# CurrentController.net
KiCad netlist of a schematic drawn in EAGLE
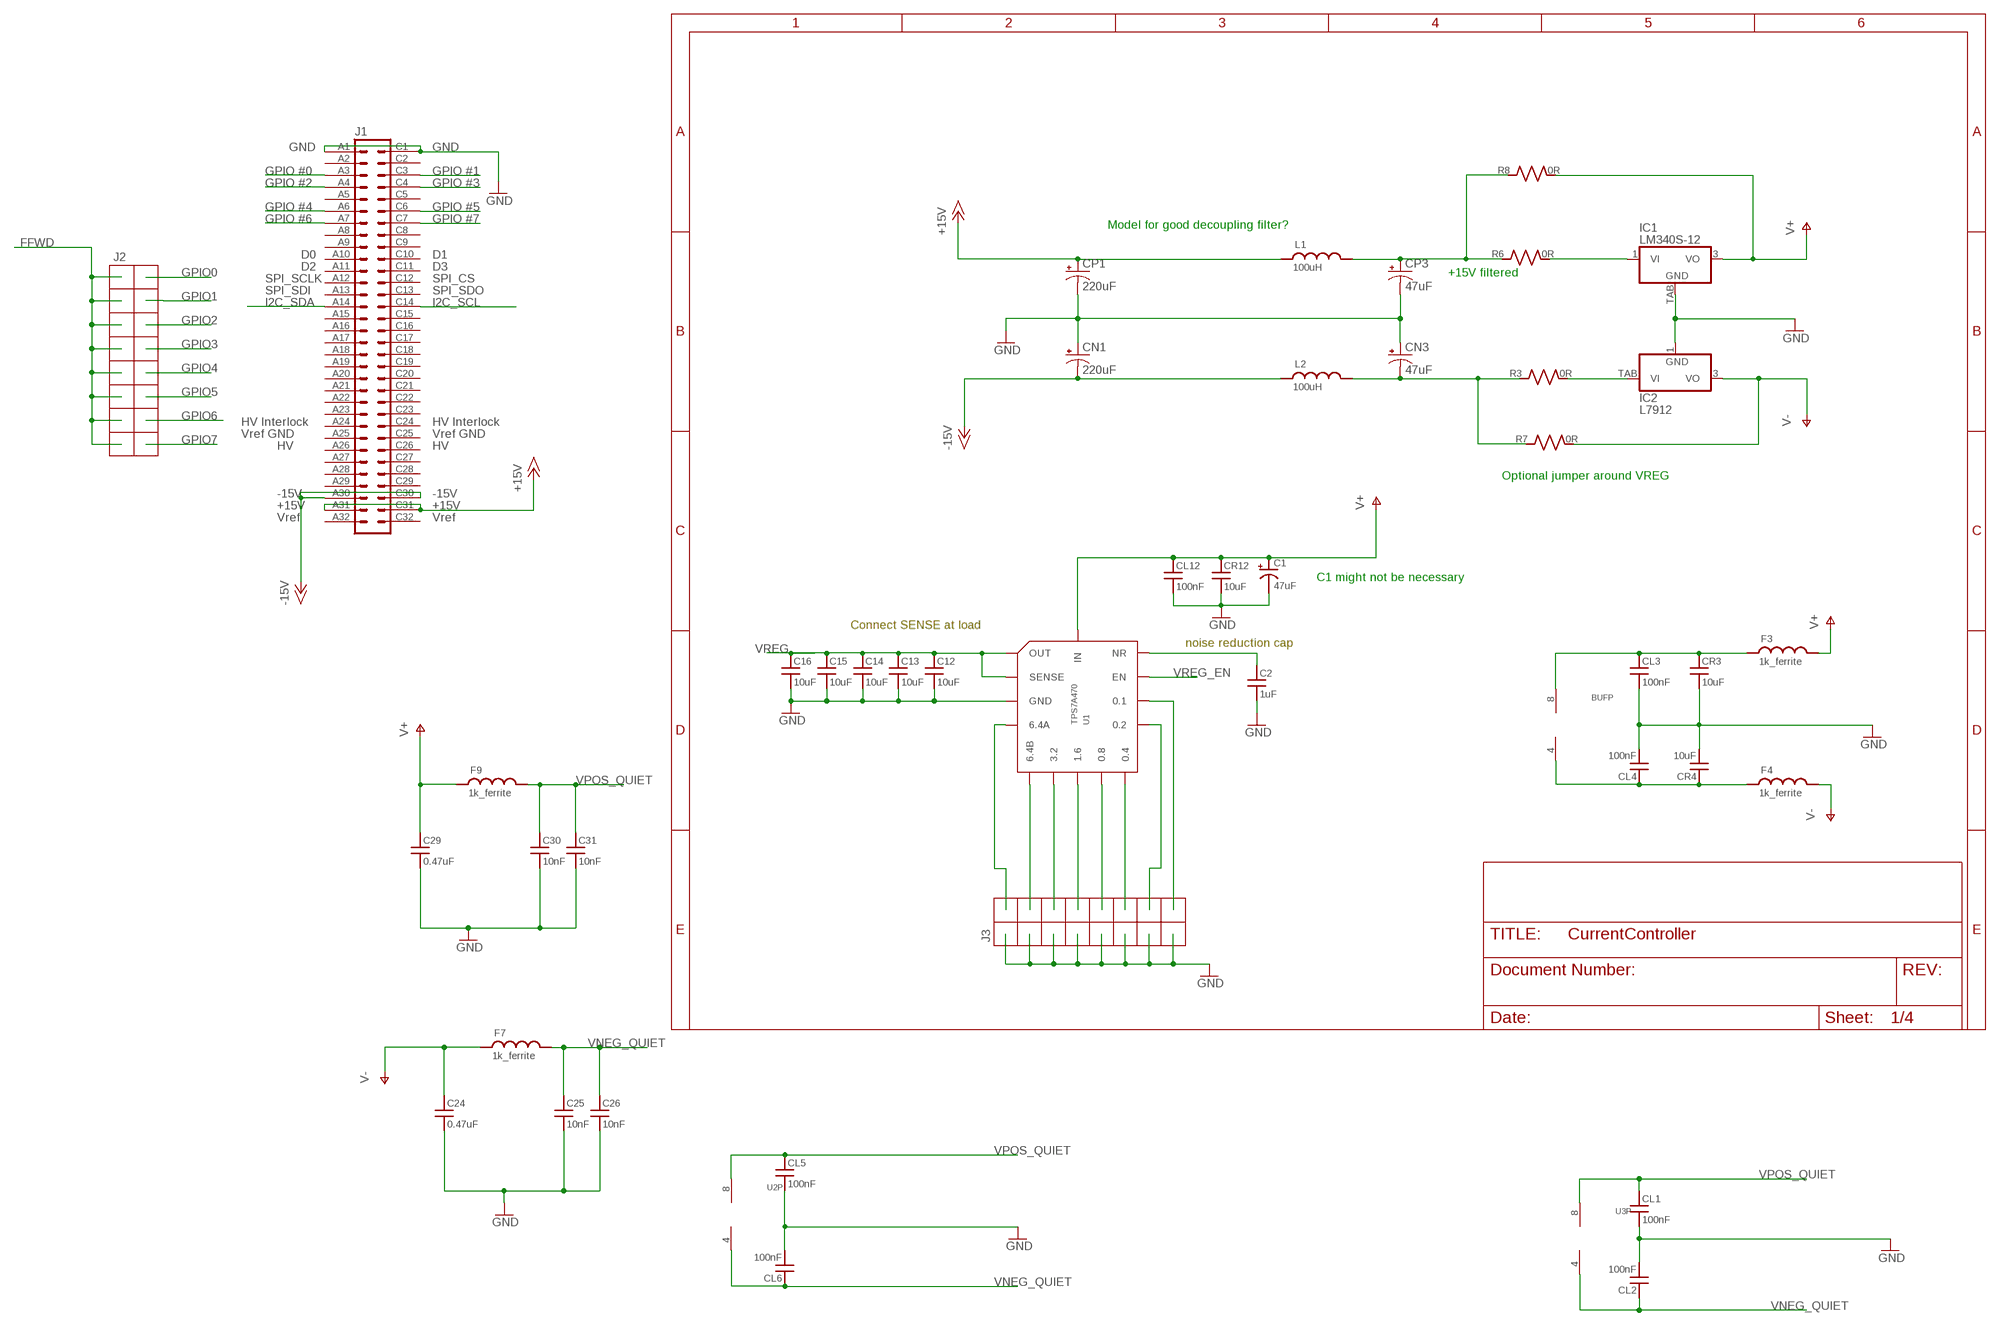
[diagram p0: schematic, sheet 1]
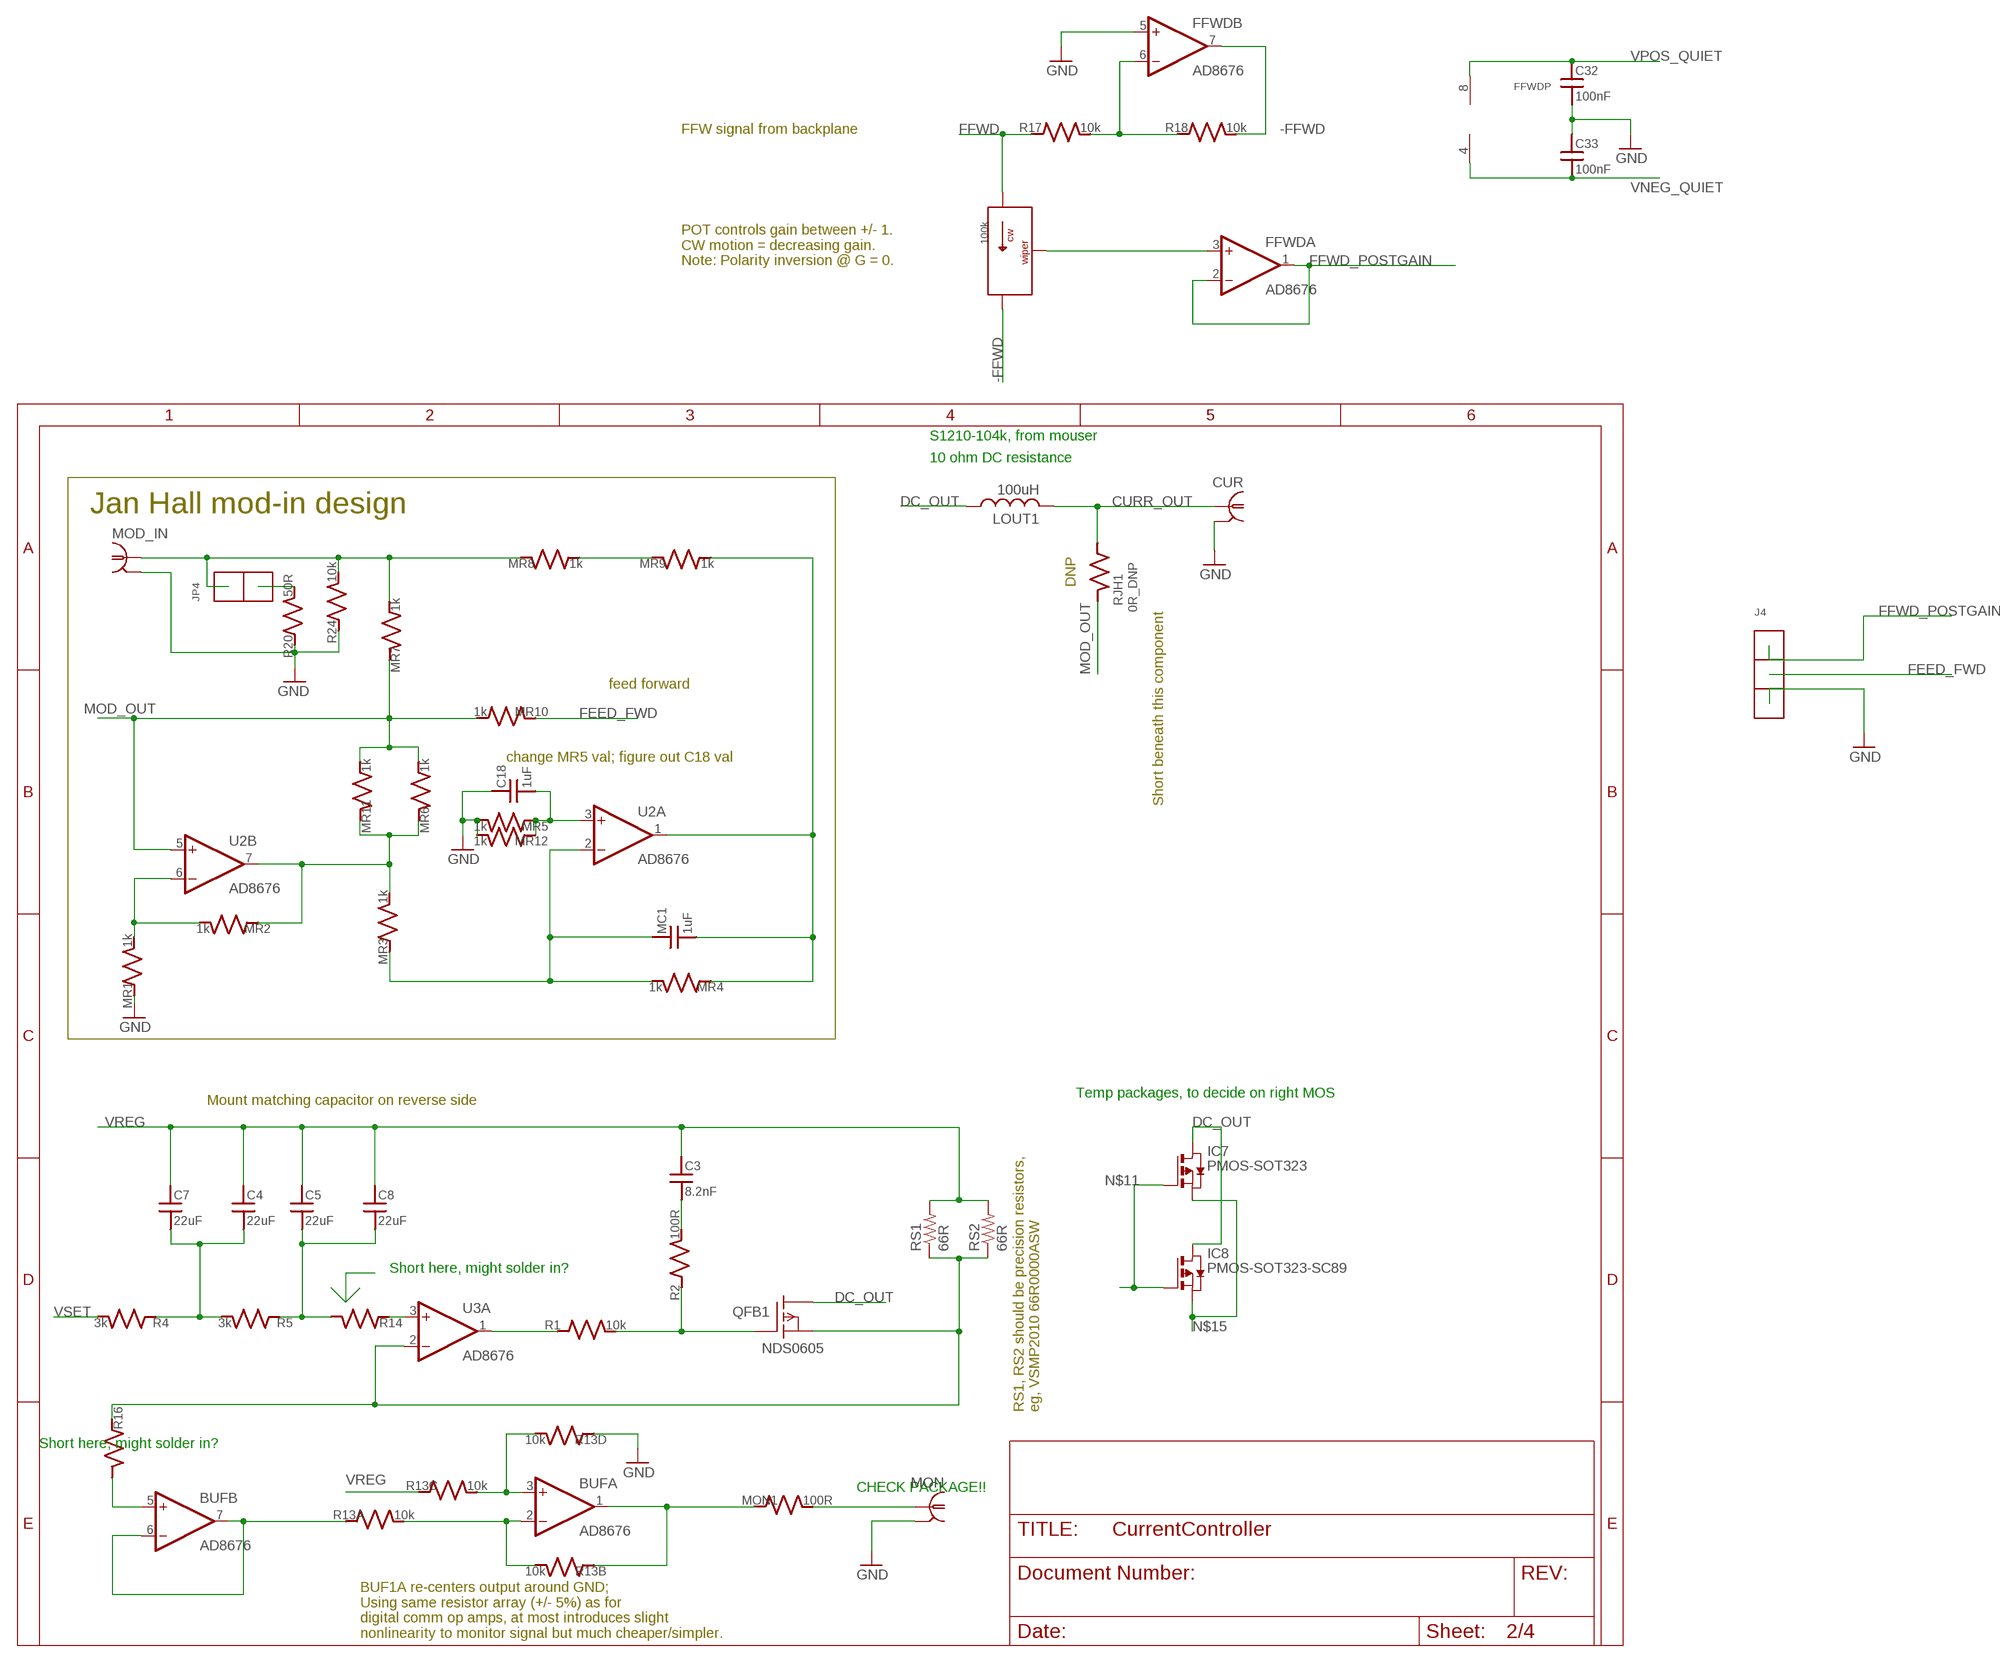
[diagram p1: schematic, sheet 2]
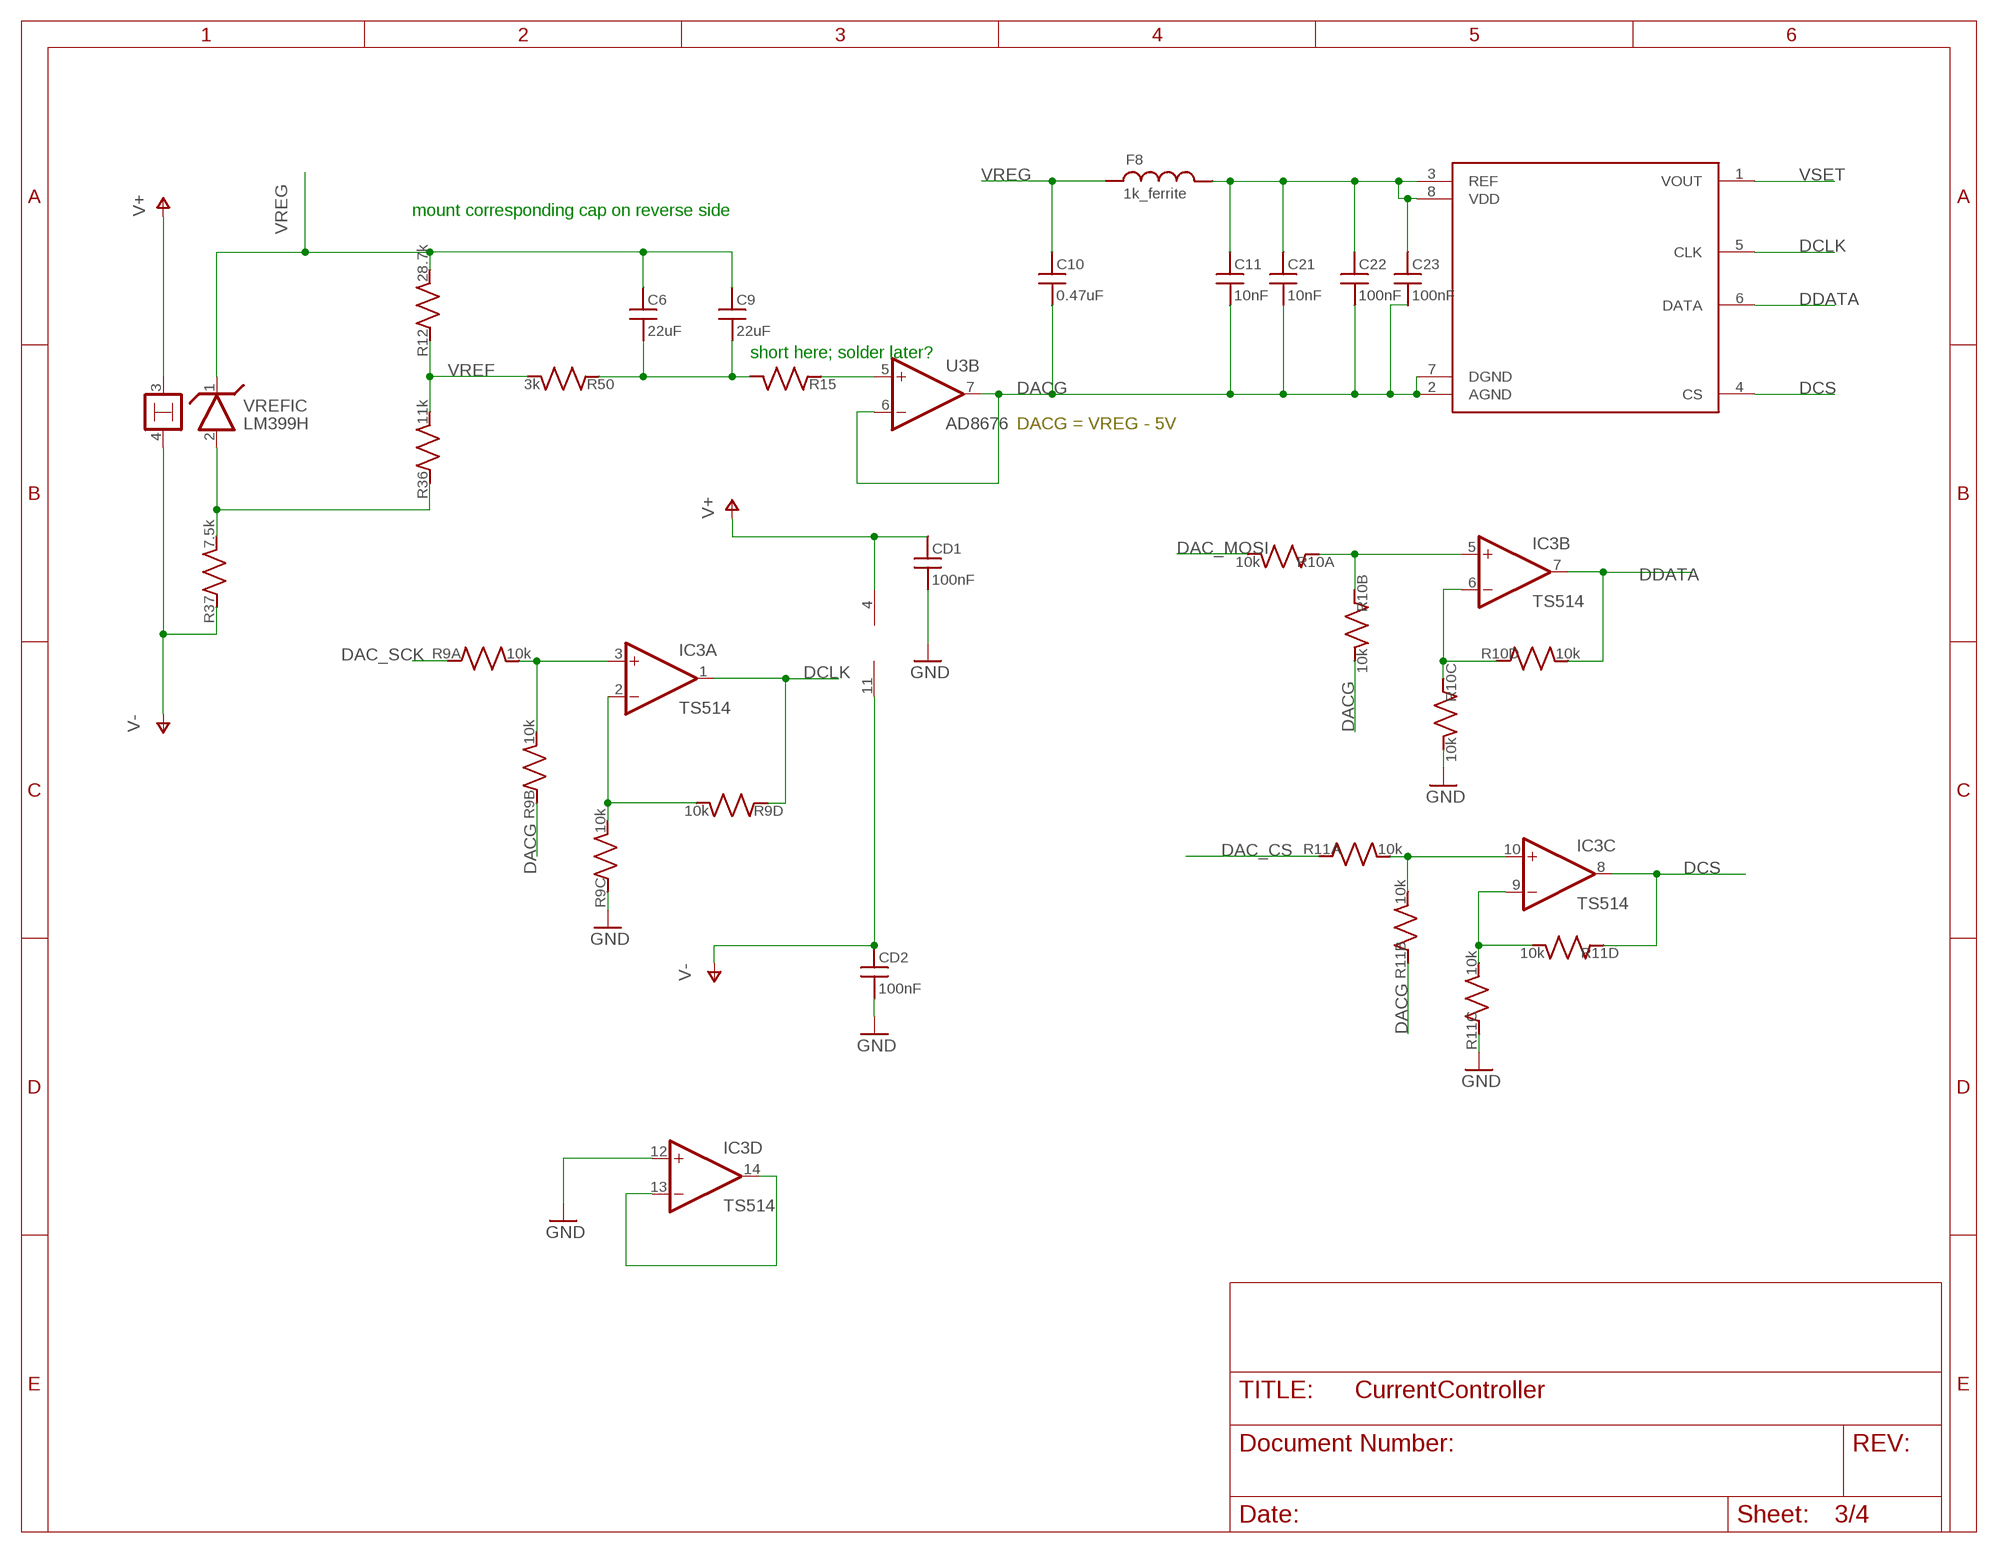
[diagram p2: schematic, sheet 3]
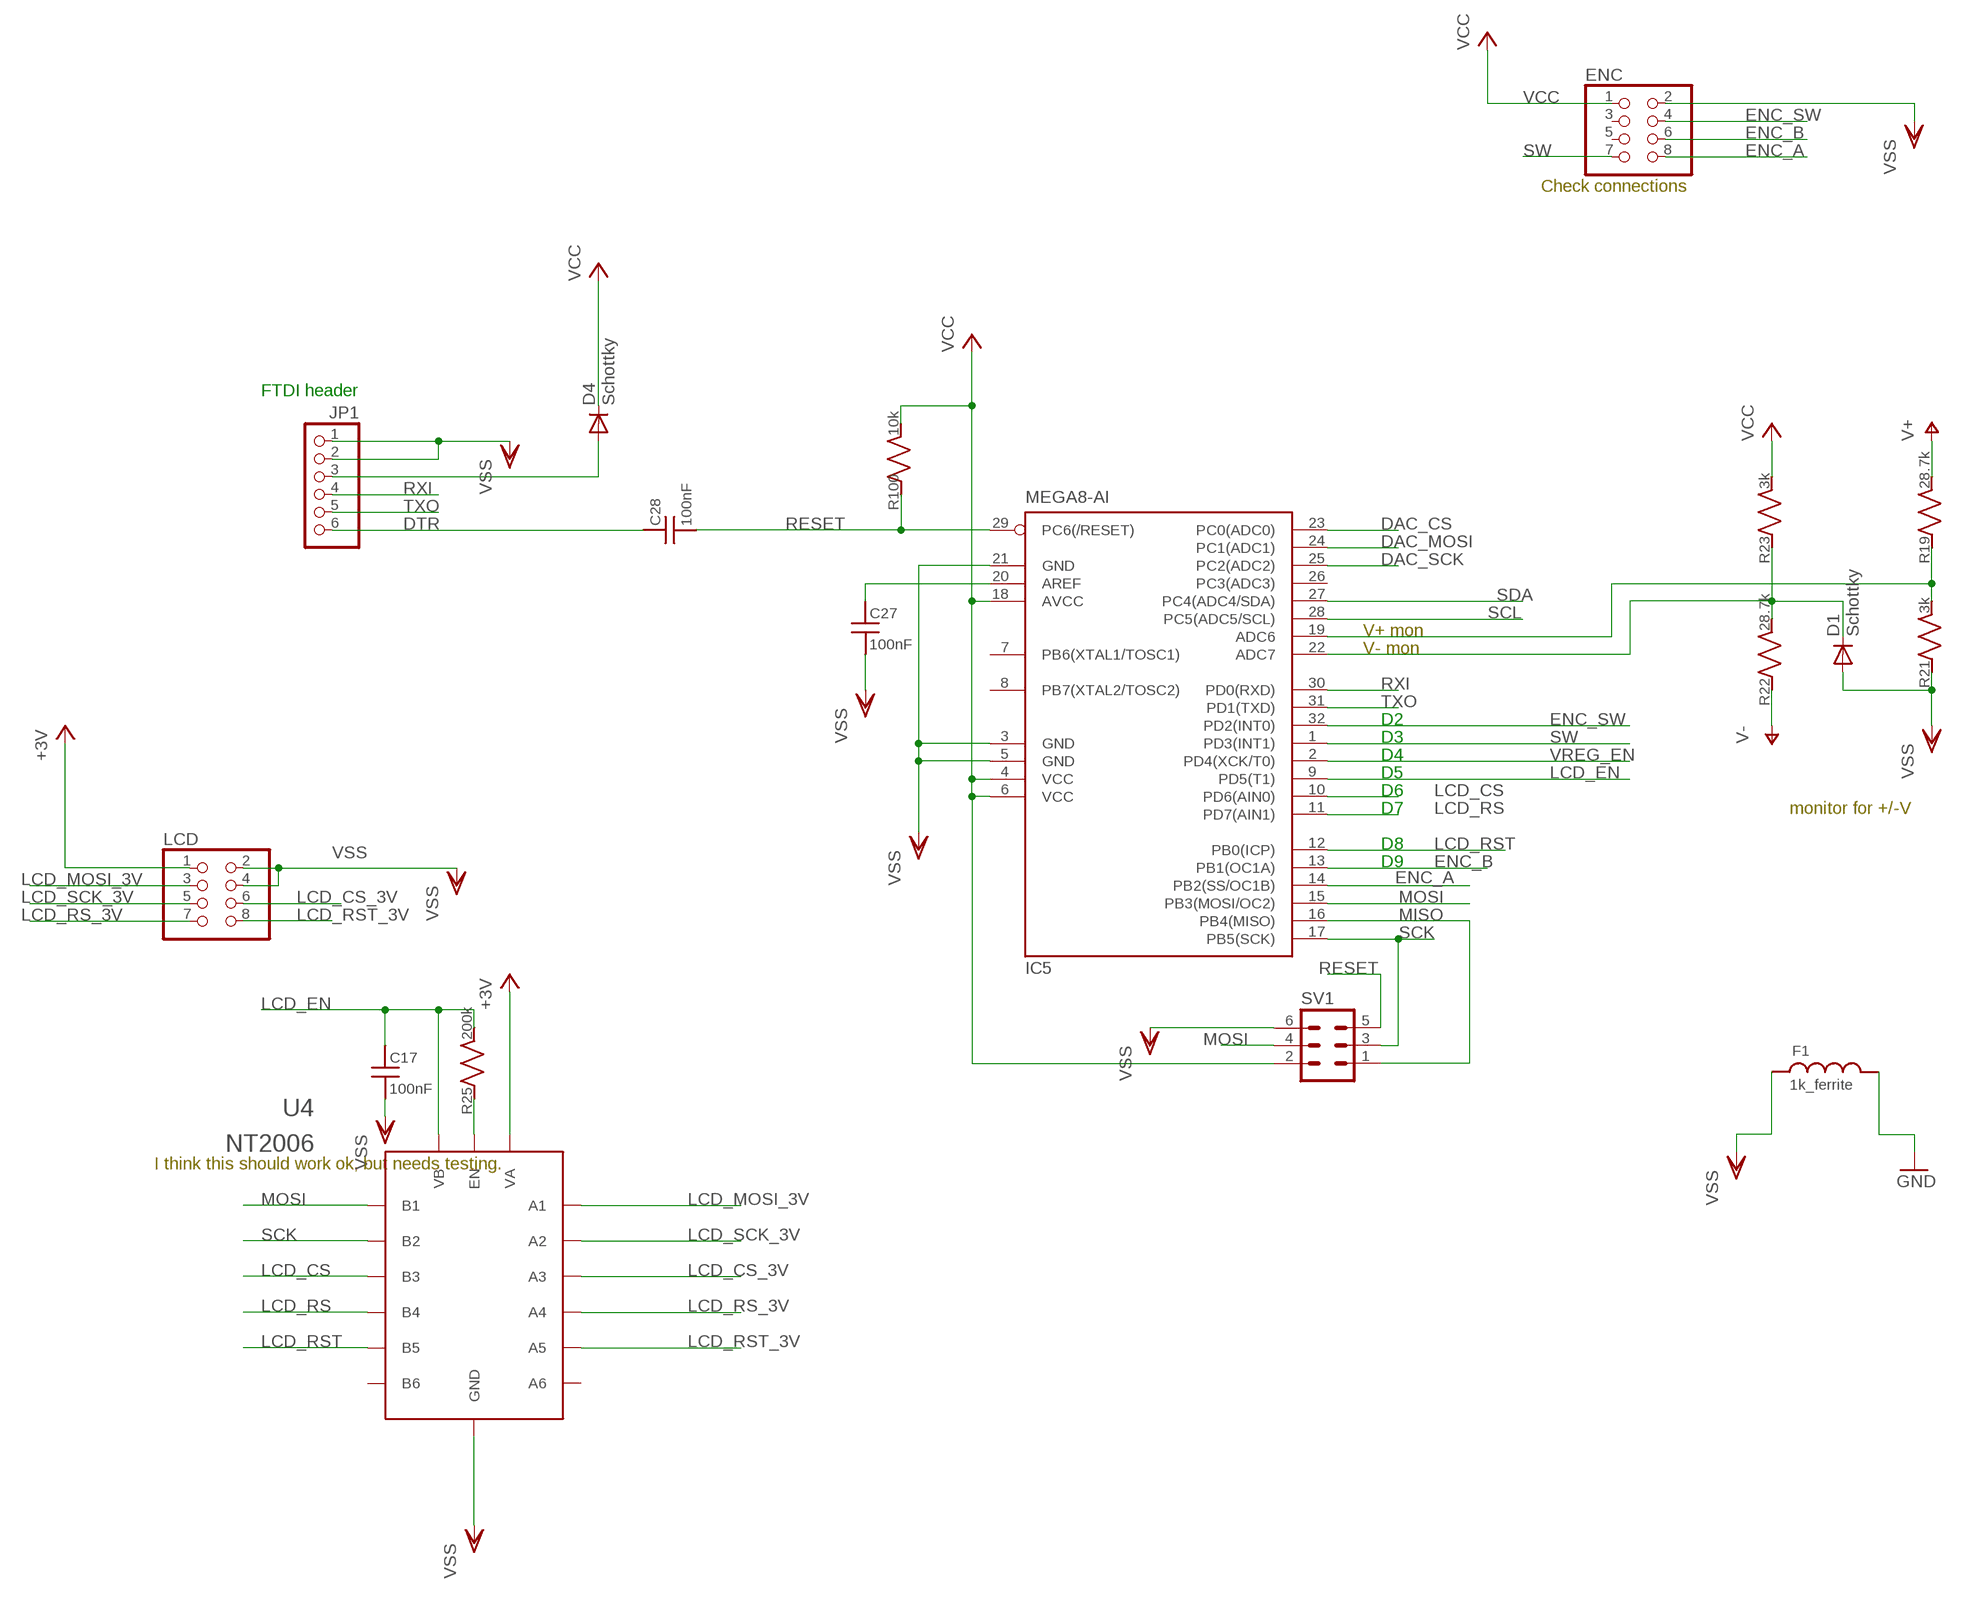
[diagram p3: schematic, sheet 4, part 1 of 2]
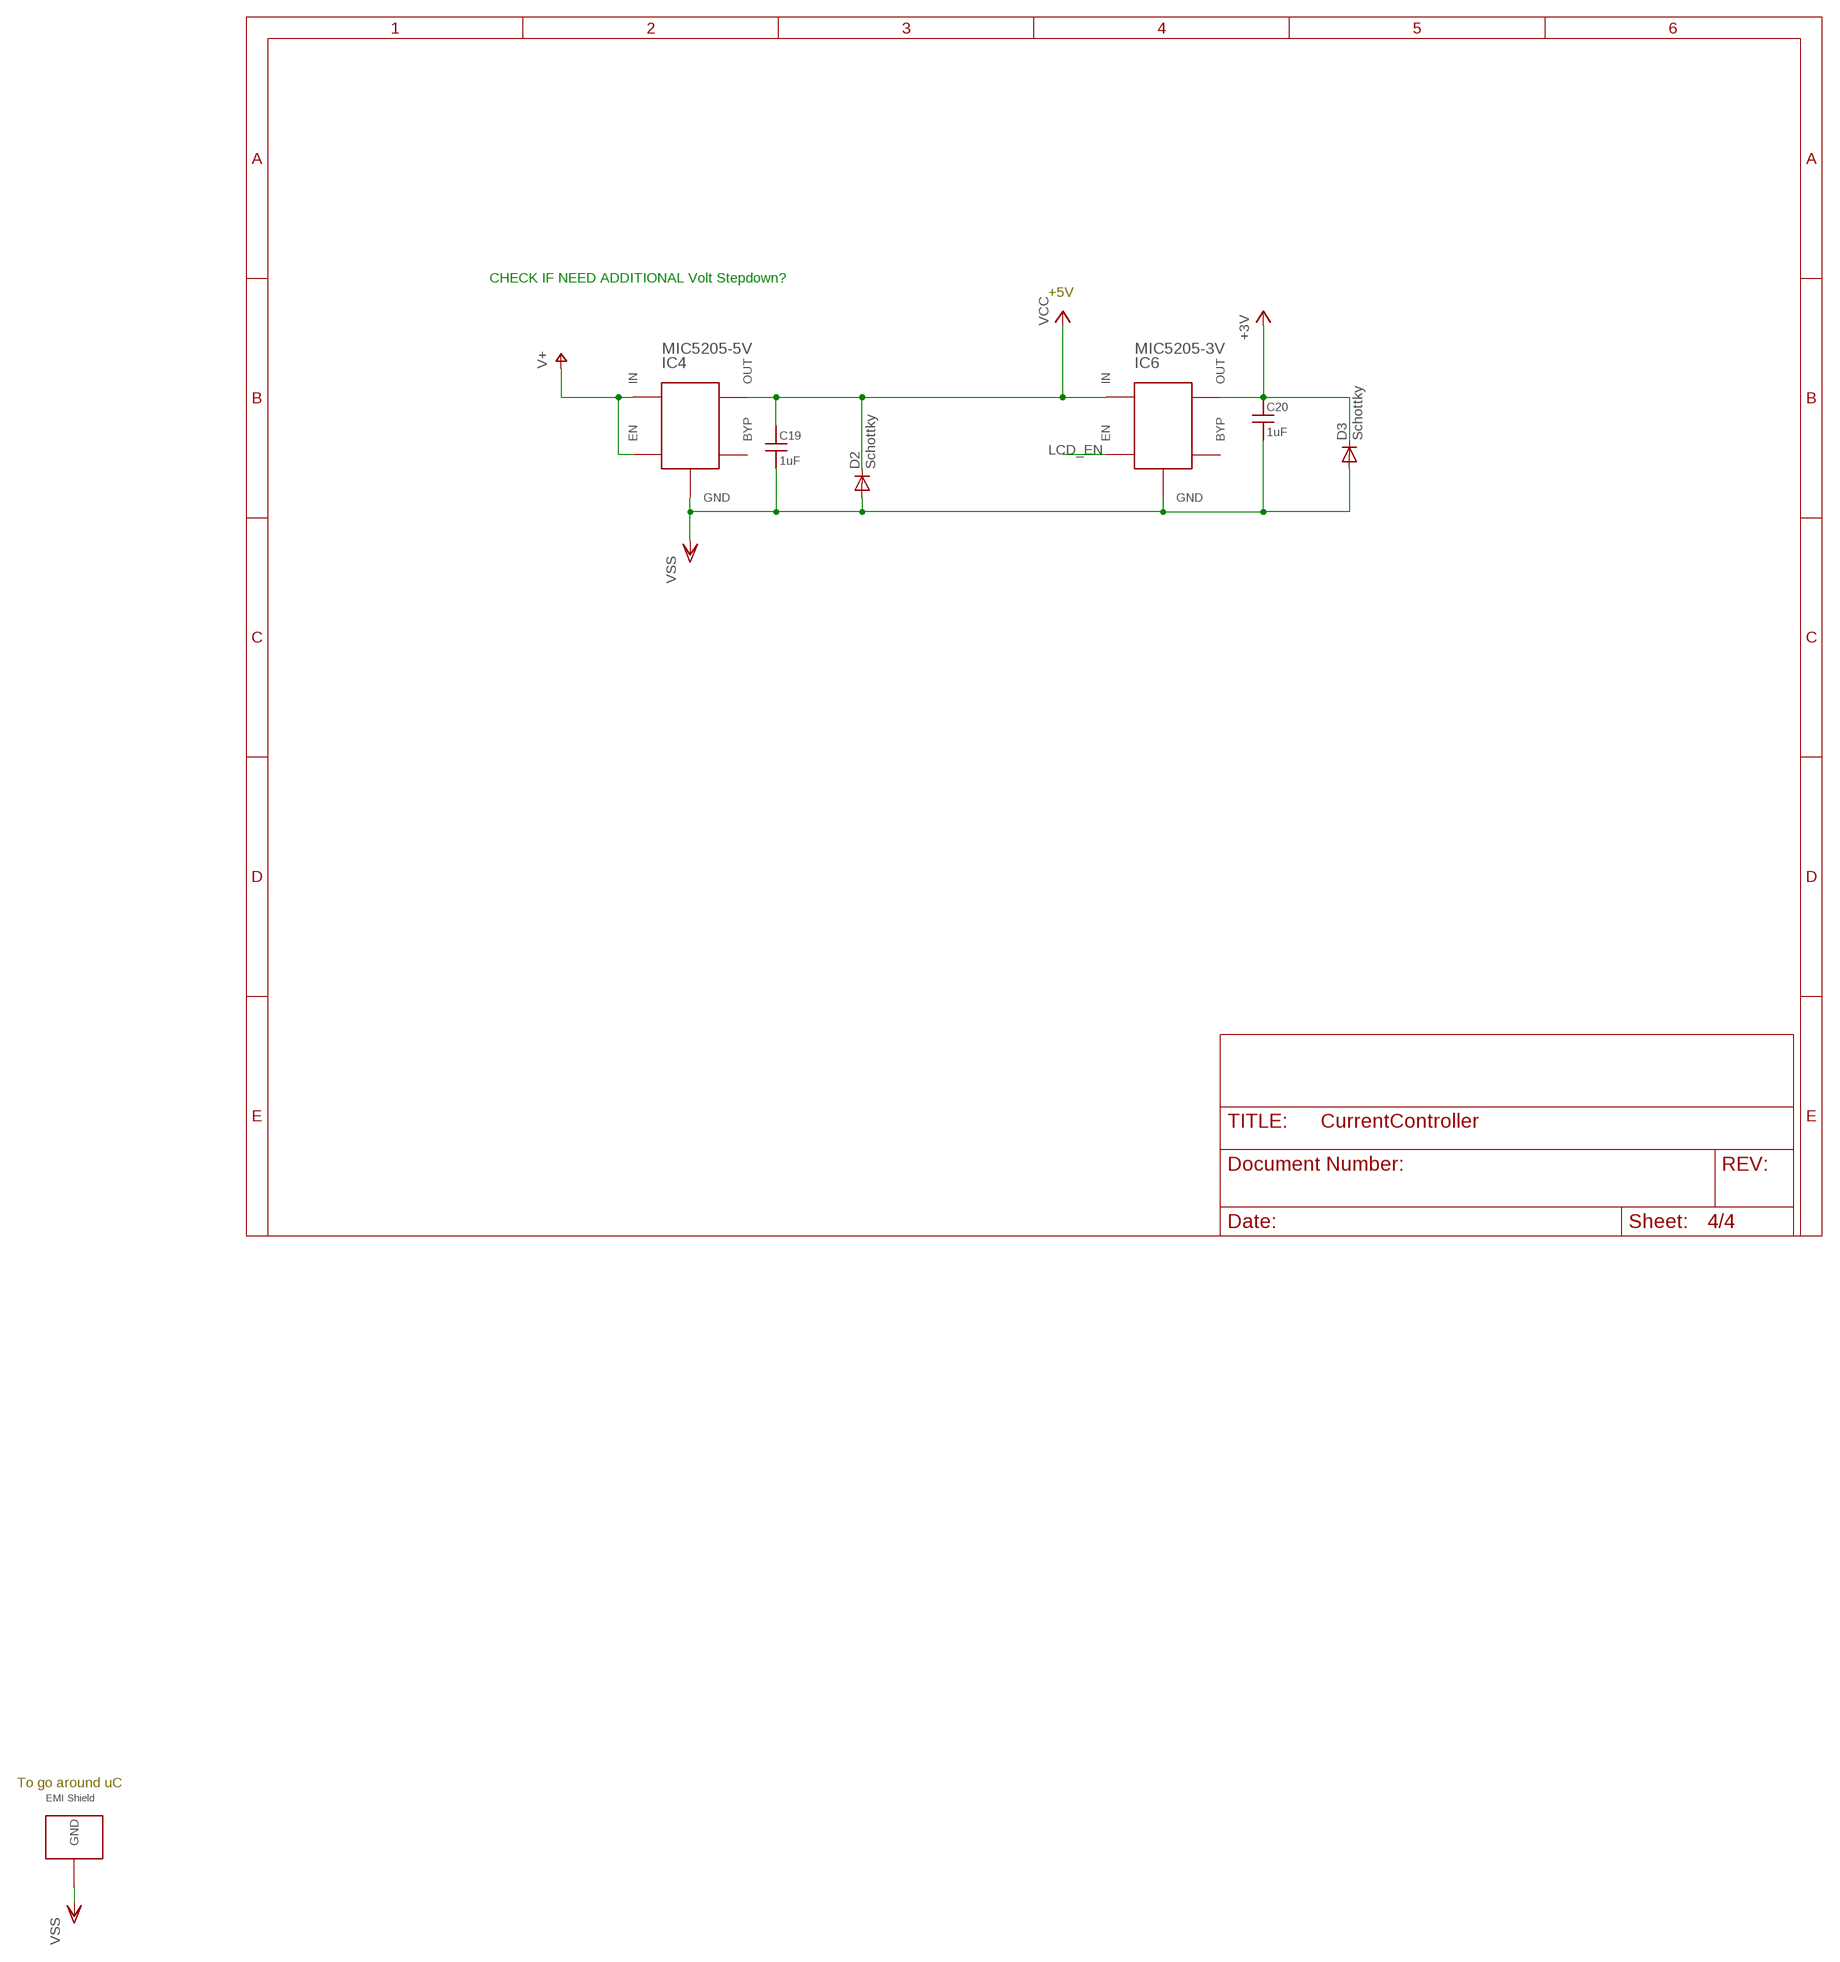
[diagram p4: schematic, sheet 4, part 2 of 2]

(export (version "E")
  (design (tool "Eeschema 10.0.6"))
  (components
    (comp (ref "C17")
      (value "100nF")
      (footprint "eagle-import:C_MLCC_0603")
      (fields (field (name "PARTNO") "C1608X7R1E104K080AA"))
      (libsource (lib "eagle-import") (part "C_MLCC_SMDCMLCC_0603"))
    )
    (comp (ref "C19")
      (value "1uF")
      (footprint "eagle-import:C_MLCC_0603")
      (fields (field (name "PARTNO") "CL10B105KA8NNNC"))
      (libsource (lib "eagle-import") (part "C_MLCC_SMDCMLCC_0603"))
    )
    (comp (ref "C20")
      (value "1uF")
      (footprint "eagle-import:C_MLCC_0603")
      (fields (field (name "PARTNO") "CL10B105KA8NNNC"))
      (libsource (lib "eagle-import") (part "C_MLCC_SMDCMLCC_0603"))
    )
    (comp (ref "C27")
      (value "100nF")
      (footprint "eagle-import:C_MLCC_0603")
      (fields (field (name "PARTNO") "C1608X7R1E104K080AA"))
      (libsource (lib "eagle-import") (part "C_MLCC_SMDCMLCC_0603"))
    )
    (comp (ref "C28")
      (value "100nF")
      (footprint "eagle-import:C_MLCC_0603")
      (fields (field (name "PARTNO") "C1608X7R1E104K080AA"))
      (libsource (lib "eagle-import") (part "C_MLCC_SMDCMLCC_0603"))
    )
    (comp (ref "D1")
      (value "Schottky")
      (footprint "eagle-import:SOD523")
      (fields (field (name "PARTNO") "PMEG3005EB,115"))
      (libsource (lib "eagle-import") (part "DIODE-SOD523"))
    )
    (comp (ref "D2")
      (value "Schottky")
      (footprint "eagle-import:SOD523")
      (fields (field (name "PARTNO") "PMEG3005EB,115"))
      (libsource (lib "eagle-import") (part "DIODE-SOD523"))
    )
    (comp (ref "D3")
      (value "Schottky")
      (footprint "eagle-import:SOD523")
      (fields (field (name "PARTNO") "PMEG3005EB,115"))
      (libsource (lib "eagle-import") (part "DIODE-SOD523"))
    )
    (comp (ref "D4")
      (value "Schottky")
      (footprint "eagle-import:SOD523")
      (fields (field (name "PARTNO") "PMEG3005EB,115"))
      (libsource (lib "eagle-import") (part "DIODE-SOD523"))
    )
    (comp (ref "ENC")
      (value "PINHD-2X4-SHROUD")
      (footprint "eagle-import:ML08")
      (fields (field (name "PARTNO") "75869-132LF"))
      (libsource (lib "eagle-import") (part "PINHD-2X4-SHROUD"))
    )
    (comp (ref "F1")
      (value "1k_ferrite")
      (footprint "eagle-import:L_FERRITE_0603")
      (fields (field (name "PARTNO") "BLM18HG102SN1D"))
      (libsource (lib "eagle-import") (part "L_FERRITE_SMDLFERRITE_0603"))
    )
    (comp (ref "IC4")
      (value "MIC5205-5V")
      (footprint "eagle-import:SOT23-5L")
      (fields (field (name "PARTNO") "MIC5205-5.0YM5-TR"))
      (libsource (lib "eagle-import") (part "MIC5205"))
    )
    (comp (ref "IC5")
      (value "MEGA8-AI")
      (footprint "eagle-import:TQFP32-08")
      (fields (field (name "MPN") "ATMEGA8-16AU") (field (name "PARTNO") "ATMEGA328P-AU"))
      (libsource (lib "eagle-import") (part "MEGA8-AI"))
    )
    (comp (ref "IC6")
      (value "MIC5205-3V")
      (footprint "eagle-import:SOT23-5L")
      (fields (field (name "PARTNO") "MIC5205-3.0YM5-TR"))
      (libsource (lib "eagle-import") (part "MIC5205"))
    )
    (comp (ref "JP1")
      (value "PINHD-1X6")
      (footprint "eagle-import:1X06")
      (fields (field (name "PARTNO") "68000-406HLF"))
      (libsource (lib "eagle-import") (part "PINHD-1X6"))
    )
    (comp (ref "LCD")
      (value "PINHD-2X4-SHROUD")
      (footprint "eagle-import:ML08")
      (fields (field (name "PARTNO") "75869-132LF"))
      (libsource (lib "eagle-import") (part "PINHD-2X4-SHROUD"))
    )
    (comp (ref "R19")
      (value "28.7k")
      (footprint "eagle-import:R_0603")
      (fields (field (name "PARTNO") "ERJ-3EKF2872V"))
      (libsource (lib "eagle-import") (part "R_SMDR0603"))
    )
    (comp (ref "R21")
      (value "3k")
      (footprint "eagle-import:R_0603")
      (fields (field (name "PARTNO") "ERJ-3EKF3001V"))
      (libsource (lib "eagle-import") (part "R_SMDR0603"))
    )
    (comp (ref "R22")
      (value "28.7k")
      (footprint "eagle-import:R_0603")
      (fields (field (name "PARTNO") "ERJ-3EKF2872V"))
      (libsource (lib "eagle-import") (part "R_SMDR0603"))
    )
    (comp (ref "R23")
      (value "3k")
      (footprint "eagle-import:R_0603")
      (fields (field (name "PARTNO") "ERJ-3EKF3001V"))
      (libsource (lib "eagle-import") (part "R_SMDR0603"))
    )
    (comp (ref "R25")
      (value "200k")
      (footprint "eagle-import:R_0603")
      (fields (field (name "PARTNO") "ERJ-3EKF2003V"))
      (libsource (lib "eagle-import") (part "R_SMDR0603"))
    )
    (comp (ref "R100")
      (value "10k")
      (footprint "eagle-import:R_0603")
      (fields (field (name "PARTNO") "ERJ-3EKF1002V"))
      (libsource (lib "eagle-import") (part "R_SMDR0603"))
    )
    (comp (ref "SV1")
      (value "MA03-2")
      (footprint "eagle-import:MA03-2")
      (fields (field (name "PARTNO") "67996-406HLF"))
      (libsource (lib "eagle-import") (part "MA03-2"))
    )
    (comp (ref "U$5")
      (value "WURTH_EMI")
      (footprint "eagle-import:WURTH_SHIELD")
      (fields (field (name "PARTNO") "36103205"))
      (libsource (lib "eagle-import") (part "WURTH_EMI"))
    )
    (comp (ref "U4")
      (value "NT2006")
      (footprint "eagle-import:HVQFN16")
      (fields (field (name "PARTNO") "NVT2006BS,118"))
      (libsource (lib "eagle-import") (part "NT2006"))
    )
    (comp (ref "C6")
      (value "22uF")
      (footprint "eagle-import:C_MLCC_0805")
      (fields (field (name "PARTNO") "C2012X5R1E226M125AC"))
      (libsource (lib "eagle-import") (part "C_MLCC_SMDCMLCC_0805"))
    )
    (comp (ref "C9")
      (value "22uF")
      (footprint "eagle-import:C_MLCC_0805")
      (fields (field (name "PARTNO") "C2012X5R1E226M125AC"))
      (libsource (lib "eagle-import") (part "C_MLCC_SMDCMLCC_0805"))
    )
    (comp (ref "C10")
      (value "0.47uF")
      (footprint "eagle-import:C_MLCC_0612")
      (fields (field (name "PARTNO") "LLL31MR71E474MA01L"))
      (libsource (lib "eagle-import") (part "C_MLCC_SMDCMLCC_0612"))
    )
    (comp (ref "C11")
      (value "10nF")
      (footprint "eagle-import:C_MLCC_0306")
      (fields (field (name "PARTNO") "03063C103KAT2A"))
      (libsource (lib "eagle-import") (part "C_MLCC_SMDCMLCC_0306"))
    )
    (comp (ref "C21")
      (value "10nF")
      (footprint "eagle-import:C_MLCC_0306")
      (fields (field (name "PARTNO") "03063C103KAT2A"))
      (libsource (lib "eagle-import") (part "C_MLCC_SMDCMLCC_0306"))
    )
    (comp (ref "C22")
      (value "100nF")
      (footprint "eagle-import:C_MLCC_0603")
      (fields (field (name "PARTNO") "C1608X7R1E104K080AA"))
      (libsource (lib "eagle-import") (part "C_MLCC_SMDCMLCC_0603"))
    )
    (comp (ref "C23")
      (value "100nF")
      (footprint "eagle-import:C_MLCC_0603")
      (fields (field (name "PARTNO") "C1608X7R1E104K080AA"))
      (libsource (lib "eagle-import") (part "C_MLCC_SMDCMLCC_0603"))
    )
    (comp (ref "CD1")
      (value "100nF")
      (footprint "eagle-import:C_MLCC_0603")
      (fields (field (name "PARTNO") "C1608X7R1E104K080AA"))
      (libsource (lib "eagle-import") (part "C_MLCC_SMDCMLCC_0603"))
    )
    (comp (ref "CD2")
      (value "100nF")
      (footprint "eagle-import:C_MLCC_0603")
      (fields (field (name "PARTNO") "C1608X7R1E104K080AA"))
      (libsource (lib "eagle-import") (part "C_MLCC_SMDCMLCC_0603"))
    )
    (comp (ref "DAC1")
      (value "AD5541")
      (footprint "eagle-import:SOIC-8")
      (fields (field (name "PARTNO") "AD5541BRZ"))
      (libsource (lib "eagle-import") (part "AD5541"))
    )
    (comp (ref "F8")
      (value "1k_ferrite")
      (footprint "eagle-import:L_FERRITE_0603")
      (fields (field (name "PARTNO") "BLM18HG102SN1D"))
      (libsource (lib "eagle-import") (part "L_FERRITE_SMDLFERRITE_0603"))
    )
    (comp (ref "IC3")
      (value "TS514")
      (footprint "eagle-import:SO14")
      (fields (field (name "PARTNO") "TS514AIDT"))
      (libsource (lib "eagle-import") (part "4AMP_P4+11D"))
    )
    (comp (ref "R9")
      (value "10k")
      (footprint "eagle-import:742_ARRAY")
      (fields (field (name "PARTNO") "742C083103JP"))
      (libsource (lib "eagle-import") (part "R_ARRAY"))
    )
    (comp (ref "R10")
      (value "10k")
      (footprint "eagle-import:742_ARRAY")
      (fields (field (name "PARTNO") "742C083103JP"))
      (libsource (lib "eagle-import") (part "R_ARRAY"))
    )
    (comp (ref "R11")
      (value "10k")
      (footprint "eagle-import:742_ARRAY")
      (fields (field (name "PARTNO") "742C083103JP"))
      (libsource (lib "eagle-import") (part "R_ARRAY"))
    )
    (comp (ref "R12")
      (value "28.7k")
      (footprint "eagle-import:R_0603")
      (fields (field (name "PARTNO") "ERJ-3EKF2872V"))
      (libsource (lib "eagle-import") (part "R_SMDR0603"))
    )
    (comp (ref "R15")
      (value "R_SMDR0603")
      (footprint "eagle-import:R_0603")
      (libsource (lib "eagle-import") (part "R_SMDR0603"))
    )
    (comp (ref "R36")
      (value "11k")
      (footprint "eagle-import:R_0603")
      (fields (field (name "PARTNO") "ERJ-3EKF1102V"))
      (libsource (lib "eagle-import") (part "R_SMDR0603"))
    )
    (comp (ref "R37")
      (value "7.5k")
      (footprint "eagle-import:R_0603")
      (fields (field (name "PARTNO") "ERJ-3EKF7501V"))
      (libsource (lib "eagle-import") (part "R_SMDR0603"))
    )
    (comp (ref "R50")
      (value "3k")
      (footprint "eagle-import:R_0603")
      (fields (field (name "PARTNO") "ERJ-3EKF3001V"))
      (libsource (lib "eagle-import") (part "R_SMDR0603"))
    )
    (comp (ref "U3")
      (value "AD8676")
      (footprint "eagle-import:MSOP08")
      (fields (field (name "PARTNO") "AD8676ARMZ"))
      (libsource (lib "eagle-import") (part "DUAL-OPAMP-AD8676_MSOP"))
    )
    (comp (ref "VREFIC")
      (value "LM399H")
      (footprint "eagle-import:TO39_4")
      (fields (field (name "PARTNO") "LM399H#PBF"))
      (libsource (lib "eagle-import") (part "LM399H"))
    )
    (comp (ref "BUF")
      (value "AD8676")
      (footprint "eagle-import:MSOP08")
      (fields (field (name "PARTNO") "AD8676ARMZ"))
      (libsource (lib "eagle-import") (part "DUAL-OPAMP-AD8676_MSOP"))
    )
    (comp (ref "C3")
      (value "8.2nF")
      (footprint "eagle-import:C_MLCC_0603")
      (fields (field (name "PARTNO") "CL10B822KB8NNNC"))
      (libsource (lib "eagle-import") (part "C_MLCC_SMDCMLCC_0603"))
    )
    (comp (ref "C4")
      (value "22uF")
      (footprint "eagle-import:C_MLCC_0805")
      (fields (field (name "PARTNO") "C2012X5R1E226M125AC"))
      (libsource (lib "eagle-import") (part "C_MLCC_SMDCMLCC_0805"))
    )
    (comp (ref "C5")
      (value "22uF")
      (footprint "eagle-import:C_MLCC_0805")
      (fields (field (name "PARTNO") "C2012X5R1E226M125AC"))
      (libsource (lib "eagle-import") (part "C_MLCC_SMDCMLCC_0805"))
    )
    (comp (ref "C7")
      (value "22uF")
      (footprint "eagle-import:C_MLCC_0805")
      (fields (field (name "PARTNO") "C2012X5R1E226M125AC"))
      (libsource (lib "eagle-import") (part "C_MLCC_SMDCMLCC_0805"))
    )
    (comp (ref "C8")
      (value "22uF")
      (footprint "eagle-import:C_MLCC_0805")
      (fields (field (name "PARTNO") "C2012X5R1E226M125AC"))
      (libsource (lib "eagle-import") (part "C_MLCC_SMDCMLCC_0805"))
    )
    (comp (ref "C18")
      (value "1uF")
      (footprint "eagle-import:C_MLCC_0603")
      (fields (field (name "PARTNO") "CL10B105KA8NNNC"))
      (libsource (lib "eagle-import") (part "C_MLCC_SMDCMLCC_0603"))
    )
    (comp (ref "C32")
      (value "100nF")
      (footprint "eagle-import:C_MLCC_0603")
      (fields (field (name "PARTNO") "C1608X7R1E104K080AA"))
      (libsource (lib "eagle-import") (part "C_MLCC_SMDCMLCC_0603"))
    )
    (comp (ref "C33")
      (value "100nF")
      (footprint "eagle-import:C_MLCC_0603")
      (fields (field (name "PARTNO") "C1608X7R1E104K080AA"))
      (libsource (lib "eagle-import") (part "C_MLCC_SMDCMLCC_0603"))
    )
    (comp (ref "CUR")
      (value "BNC-H")
      (footprint "eagle-import:BNC90")
      (fields (field (name "PARTNO") "5227161-7"))
      (libsource (lib "eagle-import") (part "BNC-H"))
    )
    (comp (ref "FFWD")
      (value "AD8676")
      (footprint "eagle-import:MSOP08")
      (fields (field (name "PARTNO") "AD8676ARMZ"))
      (libsource (lib "eagle-import") (part "DUAL-OPAMP-AD8676_MSOP"))
    )
    (comp (ref "IC7")
      (value "PMOS-SOT323")
      (footprint "eagle-import:SOT323")
      (libsource (lib "eagle-import") (part "PMOS-SOT323"))
    )
    (comp (ref "IC8")
      (value "PMOS-SOT323-SC89")
      (footprint "eagle-import:SC-89")
      (libsource (lib "eagle-import") (part "PMOS-SOT323-SC89"))
    )
    (comp (ref "J4")
      (value "1X3_LOW_PROFILE_JUMPER")
      (footprint "eagle-import:1X3_LOW_PROFILE")
      (fields (field (name "PARTNO") "NRPN031PAEN-RC"))
      (libsource (lib "eagle-import") (part "1X3_LOW_PROFILE_JUMPER"))
    )
    (comp (ref "JP4")
      (value "1X2_LOW_PROFILE_JUMPER")
      (footprint "eagle-import:1X2_LOW_PROFILE")
      (fields (field (name "PARTNO") "S5800-02-ND") (field (name "PARTNO_1") "NRPN021PAEN-RC"))
      (libsource (lib "eagle-import") (part "1X2_LOW_PROFILE_JUMPER"))
    )
    (comp (ref "LOUT1")
      (value "100uH")
      (footprint "eagle-import:L3225P")
      (fields (field (name "PARTNO") "CBC3225T680KR"))
      (libsource (lib "eagle-import") (part "L-USL3225P"))
    )
    (comp (ref "MC1")
      (value "1uF")
      (footprint "eagle-import:C_MLCC_0603")
      (fields (field (name "PARTNO") "CL10B105KA8NNNC"))
      (libsource (lib "eagle-import") (part "C_MLCC_SMDCMLCC_0603"))
    )
    (comp (ref "MOD_IN")
      (value "BNC-H")
      (footprint "eagle-import:BNC90")
      (fields (field (name "PARTNO") "5227161-7"))
      (libsource (lib "eagle-import") (part "BNC-H"))
    )
    (comp (ref "MON")
      (value "UMC")
      (footprint "eagle-import:UMC")
      (fields (field (name "PARTNO") "1909763-1"))
      (libsource (lib "eagle-import") (part "UMC"))
    )
    (comp (ref "MON1")
      (value "100R")
      (footprint "eagle-import:R_0603")
      (fields (field (name "PARTNO") "ERJ-3EKF1000V"))
      (libsource (lib "eagle-import") (part "R_SMDR0603"))
    )
    (comp (ref "MR1")
      (value "1k")
      (footprint "eagle-import:R_0805")
      (fields (field (name "PARTNO") "ERA-6ARB102V"))
      (libsource (lib "eagle-import") (part "R_SMDR0805"))
    )
    (comp (ref "MR2")
      (value "1k")
      (footprint "eagle-import:R_0805")
      (fields (field (name "PARTNO") "ERA-6ARB102V"))
      (libsource (lib "eagle-import") (part "R_SMDR0805"))
    )
    (comp (ref "MR3")
      (value "1k")
      (footprint "eagle-import:R_0805")
      (fields (field (name "PARTNO") "ERA-6ARB102V"))
      (libsource (lib "eagle-import") (part "R_SMDR0805"))
    )
    (comp (ref "MR4")
      (value "1k")
      (footprint "eagle-import:R_0805")
      (fields (field (name "PARTNO") "ERA-6ARB102V"))
      (libsource (lib "eagle-import") (part "R_SMDR0805"))
    )
    (comp (ref "MR5")
      (value "1k")
      (footprint "eagle-import:R_0805")
      (fields (field (name "PARTNO") "ERA-6ARB102V"))
      (libsource (lib "eagle-import") (part "R_SMDR0805"))
    )
    (comp (ref "MR6")
      (value "1k")
      (footprint "eagle-import:R_0805")
      (fields (field (name "PARTNO") "ERA-6ARB102V"))
      (libsource (lib "eagle-import") (part "R_SMDR0805"))
    )
    (comp (ref "MR7")
      (value "1k")
      (footprint "eagle-import:R_0805")
      (fields (field (name "PARTNO") "ERA-6ARB102V"))
      (libsource (lib "eagle-import") (part "R_SMDR0805"))
    )
    (comp (ref "MR8")
      (value "1k")
      (footprint "eagle-import:R_0805")
      (fields (field (name "PARTNO") "ERA-6ARB102V"))
      (libsource (lib "eagle-import") (part "R_SMDR0805"))
    )
    (comp (ref "MR9")
      (value "1k")
      (footprint "eagle-import:R_0805")
      (fields (field (name "PARTNO") "ERA-6ARB102V"))
      (libsource (lib "eagle-import") (part "R_SMDR0805"))
    )
    (comp (ref "MR10")
      (value "1k")
      (footprint "eagle-import:R_0805")
      (fields (field (name "PARTNO") "ERA-6ARB102V"))
      (libsource (lib "eagle-import") (part "R_SMDR0805"))
    )
    (comp (ref "MR11")
      (value "1k")
      (footprint "eagle-import:R_0805")
      (fields (field (name "PARTNO") "ERA-6ARB102V"))
      (libsource (lib "eagle-import") (part "R_SMDR0805"))
    )
    (comp (ref "MR12")
      (value "1k")
      (footprint "eagle-import:R_0805")
      (fields (field (name "PARTNO") "ERA-6ARB102V"))
      (libsource (lib "eagle-import") (part "R_SMDR0805"))
    )
    (comp (ref "QFB1")
      (value "NDS0605")
      (footprint "eagle-import:SOT-23")
      (libsource (lib "eagle-import") (part "NDS0605"))
    )
    (comp (ref "R1")
      (value "10k")
      (footprint "eagle-import:R_0603")
      (fields (field (name "PARTNO") "ERJ-3EKF1002V"))
      (libsource (lib "eagle-import") (part "R_SMDR0603"))
    )
    (comp (ref "R2")
      (value "100R")
      (footprint "eagle-import:R_0603")
      (fields (field (name "PARTNO") "ERJ-3EKF1000V"))
      (libsource (lib "eagle-import") (part "R_SMDR0603"))
    )
    (comp (ref "R4")
      (value "3k")
      (footprint "eagle-import:R_0603")
      (fields (field (name "PARTNO") "ERJ-3EKF3001V"))
      (libsource (lib "eagle-import") (part "R_SMDR0603"))
    )
    (comp (ref "R5")
      (value "3k")
      (footprint "eagle-import:R_0603")
      (fields (field (name "PARTNO") "ERJ-3EKF3001V"))
      (libsource (lib "eagle-import") (part "R_SMDR0603"))
    )
    (comp (ref "R13")
      (value "10k")
      (footprint "eagle-import:742_ARRAY")
      (fields (field (name "PARTNO") "742C083103JP"))
      (libsource (lib "eagle-import") (part "R_ARRAY"))
    )
    (comp (ref "R14")
      (value "R_SMDR0603")
      (footprint "eagle-import:R_0603")
      (libsource (lib "eagle-import") (part "R_SMDR0603"))
    )
    (comp (ref "R16")
      (value "R_SMDR0603")
      (footprint "eagle-import:R_0603")
      (libsource (lib "eagle-import") (part "R_SMDR0603"))
    )
    (comp (ref "R17")
      (value "10k")
      (footprint "eagle-import:R_0603")
      (fields (field (name "PARTNO") "ERJ-3EKF1002V"))
      (libsource (lib "eagle-import") (part "R_SMDR0603"))
    )
    (comp (ref "R18")
      (value "10k")
      (footprint "eagle-import:R_0603")
      (fields (field (name "PARTNO") "ERJ-3EKF1002V"))
      (libsource (lib "eagle-import") (part "R_SMDR0603"))
    )
    (comp (ref "R20")
      (value "50R")
      (footprint "eagle-import:R_0805")
      (fields (field (name "PARTNO") "ERJ-6ENF49R9V"))
      (libsource (lib "eagle-import") (part "R_SMDR0805"))
    )
    (comp (ref "R24")
      (value "10k")
      (footprint "eagle-import:R_0603")
      (fields (field (name "PARTNO") "ERJ-3EKF1002V"))
      (libsource (lib "eagle-import") (part "R_SMDR0603"))
    )
    (comp (ref "RJH1")
      (value "0R_DNP")
      (footprint "eagle-import:R_0603")
      (libsource (lib "eagle-import") (part "R_SMDR0603"))
    )
    (comp (ref "RS1")
      (value "66R")
      (footprint "eagle-import:R2010")
      (libsource (lib "eagle-import") (part "R-US_R2010"))
    )
    (comp (ref "RS2")
      (value "66R")
      (footprint "eagle-import:R2010")
      (libsource (lib "eagle-import") (part "R-US_R2010"))
    )
    (comp (ref "T1")
      (value "100k")
      (footprint "eagle-import:3006P")
      (fields (field (name "PARTNO") "3006P-1-104LF"))
      (libsource (lib "eagle-import") (part "BOURNS-3006P"))
    )
    (comp (ref "U2")
      (value "AD8676")
      (footprint "eagle-import:MSOP08")
      (fields (field (name "PARTNO") "AD8676ARMZ"))
      (libsource (lib "eagle-import") (part "DUAL-OPAMP-AD8676_MSOP"))
    )
    (comp (ref "C1")
      (value "47uF")
      (footprint "eagle-import:C_POL_1206")
      (libsource (lib "eagle-import") (part "C_POL_SMDCPOL_1206"))
    )
    (comp (ref "C2")
      (value "1uF")
      (footprint "eagle-import:C_MLCC_0603")
      (fields (field (name "PARTNO") "CL10B105KA8NNNC"))
      (libsource (lib "eagle-import") (part "C_MLCC_SMDCMLCC_0603"))
    )
    (comp (ref "C12")
      (value "10uF")
      (footprint "eagle-import:C_MLCC_0805")
      (fields (field (name "PARTNO") "CL21A106KAFN3NE"))
      (libsource (lib "eagle-import") (part "C_MLCC_SMDCMLCC_0805"))
    )
    (comp (ref "C13")
      (value "10uF")
      (footprint "eagle-import:C_MLCC_0805")
      (fields (field (name "PARTNO") "CL21A106KAFN3NE"))
      (libsource (lib "eagle-import") (part "C_MLCC_SMDCMLCC_0805"))
    )
    (comp (ref "C14")
      (value "10uF")
      (footprint "eagle-import:C_MLCC_0805")
      (fields (field (name "PARTNO") "CL21A106KAFN3NE"))
      (libsource (lib "eagle-import") (part "C_MLCC_SMDCMLCC_0805"))
    )
    (comp (ref "C15")
      (value "10uF")
      (footprint "eagle-import:C_MLCC_0805")
      (fields (field (name "PARTNO") "CL21A106KAFN3NE"))
      (libsource (lib "eagle-import") (part "C_MLCC_SMDCMLCC_0805"))
    )
    (comp (ref "C16")
      (value "10uF")
      (footprint "eagle-import:C_MLCC_0805")
      (fields (field (name "PARTNO") "CL21A106KAFN3NE"))
      (libsource (lib "eagle-import") (part "C_MLCC_SMDCMLCC_0805"))
    )
    (comp (ref "C24")
      (value "0.47uF")
      (footprint "eagle-import:C_MLCC_0612")
      (fields (field (name "PARTNO") "LLL31MR71E474MA01L"))
      (libsource (lib "eagle-import") (part "C_MLCC_SMDCMLCC_0612"))
    )
    (comp (ref "C25")
      (value "10nF")
      (footprint "eagle-import:C_MLCC_0306")
      (fields (field (name "PARTNO") "03063C103KAT2A"))
      (libsource (lib "eagle-import") (part "C_MLCC_SMDCMLCC_0306"))
    )
    (comp (ref "C26")
      (value "10nF")
      (footprint "eagle-import:C_MLCC_0306")
      (fields (field (name "PARTNO") "03063C103KAT2A"))
      (libsource (lib "eagle-import") (part "C_MLCC_SMDCMLCC_0306"))
    )
    (comp (ref "C29")
      (value "0.47uF")
      (footprint "eagle-import:C_MLCC_0612")
      (fields (field (name "PARTNO") "LLL31MR71E474MA01L"))
      (libsource (lib "eagle-import") (part "C_MLCC_SMDCMLCC_0612"))
    )
    (comp (ref "C30")
      (value "10nF")
      (footprint "eagle-import:C_MLCC_0306")
      (fields (field (name "PARTNO") "03063C103KAT2A"))
      (libsource (lib "eagle-import") (part "C_MLCC_SMDCMLCC_0306"))
    )
    (comp (ref "C31")
      (value "10nF")
      (footprint "eagle-import:C_MLCC_0306")
      (fields (field (name "PARTNO") "03063C103KAT2A"))
      (libsource (lib "eagle-import") (part "C_MLCC_SMDCMLCC_0306"))
    )
    (comp (ref "CL1")
      (value "100nF")
      (footprint "eagle-import:C_MLCC_0603")
      (fields (field (name "PARTNO") "C1608X7R1E104K080AA"))
      (libsource (lib "eagle-import") (part "C_MLCC_SMDCMLCC_0603"))
    )
    (comp (ref "CL2")
      (value "100nF")
      (footprint "eagle-import:C_MLCC_0603")
      (fields (field (name "PARTNO") "C1608X7R1E104K080AA"))
      (libsource (lib "eagle-import") (part "C_MLCC_SMDCMLCC_0603"))
    )
    (comp (ref "CL3")
      (value "100nF")
      (footprint "eagle-import:C_MLCC_0603")
      (fields (field (name "PARTNO") "C1608X7R1E104K080AA"))
      (libsource (lib "eagle-import") (part "C_MLCC_SMDCMLCC_0603"))
    )
    (comp (ref "CL4")
      (value "100nF")
      (footprint "eagle-import:C_MLCC_0603")
      (fields (field (name "PARTNO") "C1608X7R1E104K080AA"))
      (libsource (lib "eagle-import") (part "C_MLCC_SMDCMLCC_0603"))
    )
    (comp (ref "CL5")
      (value "100nF")
      (footprint "eagle-import:C_MLCC_0603")
      (fields (field (name "PARTNO") "C1608X7R1E104K080AA"))
      (libsource (lib "eagle-import") (part "C_MLCC_SMDCMLCC_0603"))
    )
    (comp (ref "CL6")
      (value "100nF")
      (footprint "eagle-import:C_MLCC_0603")
      (fields (field (name "PARTNO") "C1608X7R1E104K080AA"))
      (libsource (lib "eagle-import") (part "C_MLCC_SMDCMLCC_0603"))
    )
    (comp (ref "CL12")
      (value "100nF")
      (footprint "eagle-import:C_MLCC_0603")
      (fields (field (name "PARTNO") "C1608X7R1E104K080AA"))
      (libsource (lib "eagle-import") (part "C_MLCC_SMDCMLCC_0603"))
    )
    (comp (ref "CN1")
      (value "220uF")
      (footprint "eagle-import:PANASONIC_F")
      (fields (field (name "PARTNO") "EEE-1VA221UP"))
      (libsource (lib "eagle-import") (part "CPOL-USF"))
    )
    (comp (ref "CN3")
      (value "47uF")
      (footprint "eagle-import:CT7343")
      (fields (field (name "PARTNO") "T491D476M025AT"))
      (libsource (lib "eagle-import") (part "CPOL-USCT7343"))
    )
    (comp (ref "CP1")
      (value "220uF")
      (footprint "eagle-import:PANASONIC_F")
      (fields (field (name "PARTNO") "EEE-1VA221UP"))
      (libsource (lib "eagle-import") (part "CPOL-USF"))
    )
    (comp (ref "CP3")
      (value "47uF")
      (footprint "eagle-import:CT7343")
      (fields (field (name "PARTNO") "T491D476M025AT"))
      (libsource (lib "eagle-import") (part "CPOL-USCT7343"))
    )
    (comp (ref "CR3")
      (value "10uF")
      (footprint "eagle-import:C_MLCC_0805")
      (fields (field (name "PARTNO") "CL21A106KAFN3NE"))
      (libsource (lib "eagle-import") (part "C_MLCC_SMDCMLCC_0805"))
    )
    (comp (ref "CR4")
      (value "10uF")
      (footprint "eagle-import:C_MLCC_0805")
      (fields (field (name "PARTNO") "CL21A106KAFN3NE"))
      (libsource (lib "eagle-import") (part "C_MLCC_SMDCMLCC_0805"))
    )
    (comp (ref "CR12")
      (value "10uF")
      (footprint "eagle-import:C_MLCC_0805")
      (fields (field (name "PARTNO") "CL21A106KAFN3NE"))
      (libsource (lib "eagle-import") (part "C_MLCC_SMDCMLCC_0805"))
    )
    (comp (ref "F3")
      (value "1k_ferrite")
      (footprint "eagle-import:L_FERRITE_0603")
      (fields (field (name "PARTNO") "BLM18HG102SN1D"))
      (libsource (lib "eagle-import") (part "L_FERRITE_SMDLFERRITE_0603"))
    )
    (comp (ref "F4")
      (value "1k_ferrite")
      (footprint "eagle-import:L_FERRITE_0603")
      (fields (field (name "PARTNO") "BLM18HG102SN1D"))
      (libsource (lib "eagle-import") (part "L_FERRITE_SMDLFERRITE_0603"))
    )
    (comp (ref "F7")
      (value "1k_ferrite")
      (footprint "eagle-import:L_FERRITE_0603")
      (fields (field (name "PARTNO") "BLM18HG102SN1D"))
      (libsource (lib "eagle-import") (part "L_FERRITE_SMDLFERRITE_0603"))
    )
    (comp (ref "F9")
      (value "1k_ferrite")
      (footprint "eagle-import:L_FERRITE_0603")
      (fields (field (name "PARTNO") "BLM18HG102SN1D"))
      (libsource (lib "eagle-import") (part "L_FERRITE_SMDLFERRITE_0603"))
    )
    (comp (ref "IC1")
      (value "LM340S-12")
      (footprint "eagle-import:TO263-3")
      (fields (field (name "PARTNO") "LM340S-12/NOPB"))
      (libsource (lib "eagle-import") (part "LM340?-S12"))
    )
    (comp (ref "IC2")
      (value "L7912")
      (footprint "eagle-import:TO223-3")
      (fields (field (name "PARTNO") "MC7912CD2TG"))
      (libsource (lib "eagle-import") (part "L7912"))
    )
    (comp (ref "J1")
      (value "VG64C")
      (footprint "eagle-import:VG64-CUTOUT")
      (fields (field (name "PARTNO") "5650945-5"))
      (libsource (lib "eagle-import") (part "VG64C"))
    )
    (comp (ref "J2")
      (value "2X8_LOW_PROFILE_JUMPER")
      (footprint "eagle-import:2X8_LOW_PROFILE_JUMPER_MATRIX")
      (fields (field (name "PARTNO") "A3B-16PA-2DSA(71)"))
      (libsource (lib "eagle-import") (part "2X8_LOW_PROFILE_JUMPER"))
    )
    (comp (ref "J3")
      (value "2X8_LOW_PROFILE_JUMPER")
      (footprint "eagle-import:2X8_LOW_PROFILE_JUMPER_MATRIX")
      (fields (field (name "PARTNO") "A3B-16PA-2DSA(71)"))
      (libsource (lib "eagle-import") (part "2X8_LOW_PROFILE_JUMPER"))
    )
    (comp (ref "L1")
      (value "100uH")
      (footprint "eagle-import:WURTH_1280")
      (fields (field (name "PARTNO") "74477020"))
      (libsource (lib "eagle-import") (part "WURTH_74477020"))
    )
    (comp (ref "L2")
      (value "100uH")
      (footprint "eagle-import:WURTH_1280")
      (fields (field (name "PARTNO") "74477020"))
      (libsource (lib "eagle-import") (part "WURTH_74477020"))
    )
    (comp (ref "R3")
      (value "0R")
      (footprint "eagle-import:R_1206")
      (fields (field (name "PARTNO") "ERJ-8GEY0R00V"))
      (libsource (lib "eagle-import") (part "R_SMDR1206"))
    )
    (comp (ref "R6")
      (value "0R")
      (footprint "eagle-import:R_1206")
      (fields (field (name "PARTNO") "ERJ-8GEY0R00V"))
      (libsource (lib "eagle-import") (part "R_SMDR1206"))
    )
    (comp (ref "R7")
      (value "0R")
      (footprint "eagle-import:R_1206")
      (fields (field (name "PARTNO") "ERJ-8GEY0R00V"))
      (libsource (lib "eagle-import") (part "R_SMDR1206"))
    )
    (comp (ref "R8")
      (value "0R")
      (footprint "eagle-import:R_1206")
      (fields (field (name "PARTNO") "ERJ-8GEY0R00V"))
      (libsource (lib "eagle-import") (part "R_SMDR1206"))
    )
    (comp (ref "U1")
      (value "TPS7A470")
      (footprint "eagle-import:S-PVQFN-N20")
      (fields (field (name "PARTNO") "TPS7A4701RGWT"))
      (libsource (lib "eagle-import") (part "TPS7A470"))
    )
  )
  (nets
    (net (code "1") (name "+3V") (class "Default")
      (node (ref "C20") (pin "P$1") (pinfunction "1_P$1") (pintype "passive"))
      (node (ref "D3") (pin "C") (pinfunction "C_C") (pintype "passive"))
      (node (ref "IC6") (pin "5") (pinfunction "OUT_5") (pintype "bidirectional"))
      (node (ref "LCD") (pin "1") (pinfunction "1_1") (pintype "passive"))
      (node (ref "U4") (pin "16") (pinfunction "VA_16") (pintype "bidirectional"))
    )
    (net (code "2") (name "+15V") (class "Default")
      (node (ref "CP1") (pin "+") (pinfunction "+_+") (pintype "passive"))
      (node (ref "J1") (pin "A31") (pinfunction "A31_A31") (pintype "passive"))
      (node (ref "J1") (pin "C31") (pinfunction "C31_C31") (pintype "passive"))
      (node (ref "L1") (pin "P$1") (pinfunction "1_P$1") (pintype "passive"))
    )
    (net (code "3") (name "-15V") (class "Default")
      (node (ref "CN1") (pin "-") (pinfunction "-_-") (pintype "passive"))
      (node (ref "J1") (pin "A30") (pinfunction "A30_A30") (pintype "passive"))
      (node (ref "J1") (pin "C30") (pinfunction "C30_C30") (pintype "passive"))
      (node (ref "L2") (pin "P$1") (pinfunction "1_P$1") (pintype "passive"))
    )
    (net (code "4") (name "-FFWD") (class "Default")
      (node (ref "FFWD") (pin "7") (pinfunction "OUT_7") (pintype "output"))
      (node (ref "R18") (pin "P$2") (pinfunction "2_P$2") (pintype "passive"))
      (node (ref "T1") (pin "P$3") (pinfunction "P$3_P$3") (pintype "bidirectional"))
    )
    (net (code "5") (name "CURR_OUT") (class "Default")
      (node (ref "CUR") (pin "1") (pinfunction "1_1") (pintype "passive"))
      (node (ref "LOUT1") (pin "2") (pinfunction "2_2") (pintype "passive"))
      (node (ref "RJH1") (pin "P$1") (pinfunction "1_P$1") (pintype "passive"))
    )
    (net (code "6") (name "DACG") (class "Default")
      (node (ref "C10") (pin "P$2") (pinfunction "2_P$2") (pintype "passive"))
      (node (ref "C11") (pin "P$2") (pinfunction "2_P$2") (pintype "passive"))
      (node (ref "C21") (pin "P$2") (pinfunction "2_P$2") (pintype "passive"))
      (node (ref "C22") (pin "P$2") (pinfunction "2_P$2") (pintype "passive"))
      (node (ref "C23") (pin "P$2") (pinfunction "2_P$2") (pintype "passive"))
      (node (ref "DAC1") (pin "2") (pinfunction "AGND_2") (pintype "bidirectional"))
      (node (ref "DAC1") (pin "7") (pinfunction "DGND_7") (pintype "bidirectional"))
      (node (ref "R10") (pin "P$4") (pinfunction "2_P$4") (pintype "passive"))
      (node (ref "R11") (pin "P$3") (pinfunction "1_P$3") (pintype "passive"))
      (node (ref "R9") (pin "P$3") (pinfunction "1_P$3") (pintype "passive"))
      (node (ref "U3") (pin "6") (pinfunction "-IN_6") (pintype "input"))
      (node (ref "U3") (pin "7") (pinfunction "OUT_7") (pintype "output"))
    )
    (net (code "7") (name "DAC_CS") (class "Default")
      (node (ref "IC5") (pin "23") (pinfunction "PC0(ADC0)_23") (pintype "bidirectional"))
      (node (ref "R11") (pin "P$1") (pinfunction "1_P$1") (pintype "passive"))
    )
    (net (code "8") (name "DAC_MOSI") (class "Default")
      (node (ref "IC5") (pin "24") (pinfunction "PC1(ADC1)_24") (pintype "bidirectional"))
      (node (ref "R10") (pin "P$2") (pinfunction "2_P$2") (pintype "passive"))
    )
    (net (code "9") (name "DAC_SCK") (class "Default")
      (node (ref "IC5") (pin "25") (pinfunction "PC2(ADC2)_25") (pintype "bidirectional"))
      (node (ref "R9") (pin "P$1") (pinfunction "1_P$1") (pintype "passive"))
    )
    (net (code "10") (name "DCLK") (class "Default")
      (node (ref "DAC1") (pin "5") (pinfunction "CLK_5") (pintype "bidirectional"))
      (node (ref "IC3") (pin "1") (pinfunction "OUT_1") (pintype "output"))
      (node (ref "R9") (pin "P$7") (pinfunction "1_P$7") (pintype "passive"))
    )
    (net (code "11") (name "DCS") (class "Default")
      (node (ref "DAC1") (pin "4") (pinfunction "CS_4") (pintype "bidirectional"))
      (node (ref "IC3") (pin "8") (pinfunction "OUT_8") (pintype "output"))
      (node (ref "R11") (pin "P$7") (pinfunction "1_P$7") (pintype "passive"))
    )
    (net (code "12") (name "DC_OUT") (class "Default")
      (node (ref "IC7") (pin "3") (pinfunction "D_3") (pintype "passive"))
      (node (ref "IC8") (pin "P$3") (pinfunction "D_P$3") (pintype "passive"))
      (node (ref "LOUT1") (pin "1") (pinfunction "1_1") (pintype "passive"))
      (node (ref "QFB1") (pin "3") (pinfunction "D_3") (pintype "passive"))
    )
    (net (code "13") (name "DDATA") (class "Default")
      (node (ref "DAC1") (pin "6") (pinfunction "DATA_6") (pintype "bidirectional"))
      (node (ref "IC3") (pin "7") (pinfunction "OUT_7") (pintype "output"))
      (node (ref "R10") (pin "P$8") (pinfunction "2_P$8") (pintype "passive"))
    )
    (net (code "14") (name "DTR") (class "Default")
      (node (ref "C28") (pin "P$1") (pinfunction "1_P$1") (pintype "passive"))
      (node (ref "JP1") (pin "6") (pinfunction "6_6") (pintype "passive"))
    )
    (net (code "15") (name "ENC_A") (class "Default")
      (node (ref "ENC") (pin "8") (pinfunction "8_8") (pintype "passive"))
      (node (ref "IC5") (pin "14") (pinfunction "PB2(SS/OC1B)_14") (pintype "bidirectional"))
    )
    (net (code "16") (name "ENC_B") (class "Default")
      (node (ref "ENC") (pin "6") (pinfunction "6_6") (pintype "passive"))
      (node (ref "IC5") (pin "13") (pinfunction "PB1(OC1A)_13") (pintype "bidirectional"))
    )
    (net (code "17") (name "ENC_SW") (class "Default")
      (node (ref "ENC") (pin "4") (pinfunction "4_4") (pintype "passive"))
      (node (ref "IC5") (pin "32") (pinfunction "PD2(INT0)_32") (pintype "bidirectional"))
    )
    (net (code "18") (name "FEED_FWD") (class "Default")
      (node (ref "J4") (pin "P2") (pinfunction "P$2_P2") (pintype "bidirectional"))
      (node (ref "MR10") (pin "P$1") (pinfunction "1_P$1") (pintype "passive"))
    )
    (net (code "19") (name "FFWD") (class "Default")
      (node (ref "J2") (pin "P$1") (pinfunction "P$1_P$1") (pintype "bidirectional"))
      (node (ref "J2") (pin "P$11") (pinfunction "P$11_P$11") (pintype "bidirectional"))
      (node (ref "J2") (pin "P$13") (pinfunction "P$13_P$13") (pintype "bidirectional"))
      (node (ref "J2") (pin "P$15") (pinfunction "P$15_P$15") (pintype "bidirectional"))
      (node (ref "J2") (pin "P$3") (pinfunction "P$3_P$3") (pintype "bidirectional"))
      (node (ref "J2") (pin "P$5") (pinfunction "P$5_P$5") (pintype "bidirectional"))
      (node (ref "J2") (pin "P$7") (pinfunction "P$7_P$7") (pintype "bidirectional"))
      (node (ref "J2") (pin "P$9") (pinfunction "P$9_P$9") (pintype "bidirectional"))
      (node (ref "R17") (pin "P$1") (pinfunction "1_P$1") (pintype "passive"))
      (node (ref "T1") (pin "P$1") (pinfunction "P$1_P$1") (pintype "bidirectional"))
    )
    (net (code "20") (name "FFWD_POSTGAIN") (class "Default")
      (node (ref "FFWD") (pin "1") (pinfunction "OUT_1") (pintype "output"))
      (node (ref "FFWD") (pin "2") (pinfunction "-IN_2") (pintype "input"))
      (node (ref "J4") (pin "P1") (pinfunction "P$1_P1") (pintype "bidirectional"))
    )
    (net (code "21") (name "GND") (class "Default")
      (node (ref "C1") (pin "P$2") (pinfunction "-_P$2") (pintype "passive"))
      (node (ref "C12") (pin "P$2") (pinfunction "2_P$2") (pintype "passive"))
      (node (ref "C13") (pin "P$2") (pinfunction "2_P$2") (pintype "passive"))
      (node (ref "C14") (pin "P$2") (pinfunction "2_P$2") (pintype "passive"))
      (node (ref "C15") (pin "P$2") (pinfunction "2_P$2") (pintype "passive"))
      (node (ref "C16") (pin "P$2") (pinfunction "2_P$2") (pintype "passive"))
      (node (ref "C18") (pin "P$1") (pinfunction "1_P$1") (pintype "passive"))
      (node (ref "C2") (pin "P$2") (pinfunction "2_P$2") (pintype "passive"))
      (node (ref "C24") (pin "P$2") (pinfunction "2_P$2") (pintype "passive"))
      (node (ref "C25") (pin "P$2") (pinfunction "2_P$2") (pintype "passive"))
      (node (ref "C26") (pin "P$2") (pinfunction "2_P$2") (pintype "passive"))
      (node (ref "C29") (pin "P$2") (pinfunction "2_P$2") (pintype "passive"))
      (node (ref "C30") (pin "P$2") (pinfunction "2_P$2") (pintype "passive"))
      (node (ref "C31") (pin "P$2") (pinfunction "2_P$2") (pintype "passive"))
      (node (ref "C32") (pin "P$2") (pinfunction "2_P$2") (pintype "passive"))
      (node (ref "C33") (pin "P$1") (pinfunction "1_P$1") (pintype "passive"))
      (node (ref "CD1") (pin "P$2") (pinfunction "2_P$2") (pintype "passive"))
      (node (ref "CD2") (pin "P$2") (pinfunction "2_P$2") (pintype "passive"))
      (node (ref "CL1") (pin "P$2") (pinfunction "2_P$2") (pintype "passive"))
      (node (ref "CL12") (pin "P$2") (pinfunction "2_P$2") (pintype "passive"))
      (node (ref "CL2") (pin "P$2") (pinfunction "2_P$2") (pintype "passive"))
      (node (ref "CL3") (pin "P$2") (pinfunction "2_P$2") (pintype "passive"))
      (node (ref "CL4") (pin "P$2") (pinfunction "2_P$2") (pintype "passive"))
      (node (ref "CL5") (pin "P$2") (pinfunction "2_P$2") (pintype "passive"))
      (node (ref "CL6") (pin "P$2") (pinfunction "2_P$2") (pintype "passive"))
      (node (ref "CN1") (pin "+") (pinfunction "+_+") (pintype "passive"))
      (node (ref "CN3") (pin "+") (pinfunction "+_+") (pintype "passive"))
      (node (ref "CP1") (pin "-") (pinfunction "-_-") (pintype "passive"))
      (node (ref "CP3") (pin "-") (pinfunction "-_-") (pintype "passive"))
      (node (ref "CR12") (pin "P$2") (pinfunction "2_P$2") (pintype "passive"))
      (node (ref "CR3") (pin "P$2") (pinfunction "2_P$2") (pintype "passive"))
      (node (ref "CR4") (pin "P$2") (pinfunction "2_P$2") (pintype "passive"))
      (node (ref "CUR") (pin "2") (pinfunction "2_2") (pintype "passive"))
      (node (ref "F1") (pin "P$2") (pinfunction "2_P$2") (pintype "passive"))
      (node (ref "FFWD") (pin "5") (pinfunction "+IN_5") (pintype "input"))
      (node (ref "IC1") (pin "TAB") (pinfunction "GND_TAB") (pintype "passive"))
      (node (ref "IC2") (pin "1") (pinfunction "GND_1") (pintype "passive"))
      (node (ref "IC3") (pin "12") (pinfunction "+IN_12") (pintype "input"))
      (node (ref "J1") (pin "A1") (pinfunction "A1_A1") (pintype "passive"))
      (node (ref "J1") (pin "C1") (pinfunction "C1_C1") (pintype "passive"))
      (node (ref "J3") (pin "P$1") (pinfunction "P$1_P$1") (pintype "bidirectional"))
      (node (ref "J3") (pin "P$11") (pinfunction "P$11_P$11") (pintype "bidirectional"))
      (node (ref "J3") (pin "P$13") (pinfunction "P$13_P$13") (pintype "bidirectional"))
      (node (ref "J3") (pin "P$15") (pinfunction "P$15_P$15") (pintype "bidirectional"))
      (node (ref "J3") (pin "P$3") (pinfunction "P$3_P$3") (pintype "bidirectional"))
      (node (ref "J3") (pin "P$5") (pinfunction "P$5_P$5") (pintype "bidirectional"))
      (node (ref "J3") (pin "P$7") (pinfunction "P$7_P$7") (pintype "bidirectional"))
      (node (ref "J3") (pin "P$9") (pinfunction "P$9_P$9") (pintype "bidirectional"))
      (node (ref "J4") (pin "P3") (pinfunction "P$3_P3") (pintype "bidirectional"))
      (node (ref "MOD_IN") (pin "2") (pinfunction "2_2") (pintype "passive"))
      (node (ref "MON") (pin "P$2") (pinfunction "2_P$2") (pintype "passive"))
      (node (ref "MON") (pin "P$3") (pinfunction "2_P$3") (pintype "passive"))
      (node (ref "MR1") (pin "P$1") (pinfunction "1_P$1") (pintype "passive"))
      (node (ref "MR12") (pin "P$2") (pinfunction "2_P$2") (pintype "passive"))
      (node (ref "MR5") (pin "P$2") (pinfunction "2_P$2") (pintype "passive"))
      (node (ref "R10") (pin "P$6") (pinfunction "2_P$6") (pintype "passive"))
      (node (ref "R11") (pin "P$5") (pinfunction "1_P$5") (pintype "passive"))
      (node (ref "R13") (pin "P$7") (pinfunction "1_P$7") (pintype "passive"))
      (node (ref "R20") (pin "P$1") (pinfunction "1_P$1") (pintype "passive"))
      (node (ref "R24") (pin "P$1") (pinfunction "1_P$1") (pintype "passive"))
      (node (ref "R9") (pin "P$5") (pinfunction "1_P$5") (pintype "passive"))
      (node (ref "U1") (pin "17") (pinfunction "GND_17") (pintype "bidirectional"))
      (node (ref "U1") (pin "18") (pinfunction "GND_18") (pintype "bidirectional"))
      (node (ref "U1") (pin "19") (pinfunction "GND_19") (pintype "bidirectional"))
      (node (ref "U1") (pin "2") (pinfunction "GND_2") (pintype "bidirectional"))
      (node (ref "U1") (pin "7") (pinfunction "GND_7") (pintype "bidirectional"))
      (node (ref "U1") (pin "EXP") (pinfunction "GND_EXP") (pintype "bidirectional"))
    )
    (net (code "22") (name "GPIO0") (class "Default")
      (node (ref "J1") (pin "A3") (pinfunction "A3_A3") (pintype "passive"))
      (node (ref "J2") (pin "P$2") (pinfunction "P$2_P$2") (pintype "bidirectional"))
    )
    (net (code "23") (name "GPIO1") (class "Default")
      (node (ref "J1") (pin "C3") (pinfunction "C3_C3") (pintype "passive"))
      (node (ref "J2") (pin "P$4") (pinfunction "P$4_P$4") (pintype "bidirectional"))
    )
    (net (code "24") (name "GPIO2") (class "Default")
      (node (ref "J1") (pin "A4") (pinfunction "A4_A4") (pintype "passive"))
      (node (ref "J2") (pin "P$6") (pinfunction "P$6_P$6") (pintype "bidirectional"))
    )
    (net (code "25") (name "GPIO3") (class "Default")
      (node (ref "J1") (pin "C4") (pinfunction "C4_C4") (pintype "passive"))
      (node (ref "J2") (pin "P$8") (pinfunction "P$8_P$8") (pintype "bidirectional"))
    )
    (net (code "26") (name "GPIO4") (class "Default")
      (node (ref "J1") (pin "A6") (pinfunction "A6_A6") (pintype "passive"))
      (node (ref "J2") (pin "P$10") (pinfunction "P$10_P$10") (pintype "bidirectional"))
    )
    (net (code "27") (name "GPIO5") (class "Default")
      (node (ref "J1") (pin "C6") (pinfunction "C6_C6") (pintype "passive"))
      (node (ref "J2") (pin "P$12") (pinfunction "P$12_P$12") (pintype "bidirectional"))
    )
    (net (code "28") (name "GPIO6") (class "Default")
      (node (ref "J1") (pin "A7") (pinfunction "A7_A7") (pintype "passive"))
      (node (ref "J2") (pin "P$14") (pinfunction "P$14_P$14") (pintype "bidirectional"))
    )
    (net (code "29") (name "GPIO7") (class "Default")
      (node (ref "J1") (pin "C7") (pinfunction "C7_C7") (pintype "passive"))
      (node (ref "J2") (pin "P$16") (pinfunction "P$16_P$16") (pintype "bidirectional"))
    )
    (net (code "30") (name "LCD_CS") (class "Default")
      (node (ref "IC5") (pin "10") (pinfunction "PD6(AIN0)_10") (pintype "bidirectional"))
      (node (ref "U4") (pin "10") (pinfunction "B3_10") (pintype "bidirectional"))
    )
    (net (code "31") (name "LCD_CS_3V") (class "Default")
      (node (ref "LCD") (pin "6") (pinfunction "6_6") (pintype "passive"))
      (node (ref "U4") (pin "3") (pinfunction "A3_3") (pintype "bidirectional"))
    )
    (net (code "32") (name "LCD_EN") (class "Default")
      (node (ref "C17") (pin "P$1") (pinfunction "1_P$1") (pintype "passive"))
      (node (ref "IC5") (pin "9") (pinfunction "PD5(T1)_9") (pintype "bidirectional"))
      (node (ref "IC6") (pin "3") (pinfunction "EN_3") (pintype "bidirectional"))
      (node (ref "R25") (pin "P$2") (pinfunction "2_P$2") (pintype "passive"))
      (node (ref "U4") (pin "13") (pinfunction "VB_13") (pintype "bidirectional"))
    )
    (net (code "33") (name "LCD_MOSI_3V") (class "Default")
      (node (ref "LCD") (pin "3") (pinfunction "3_3") (pintype "passive"))
      (node (ref "U4") (pin "1") (pinfunction "A1_1") (pintype "bidirectional"))
    )
    (net (code "34") (name "LCD_RS") (class "Default")
      (node (ref "IC5") (pin "11") (pinfunction "PD7(AIN1)_11") (pintype "bidirectional"))
      (node (ref "U4") (pin "9") (pinfunction "B4_9") (pintype "bidirectional"))
    )
    (net (code "35") (name "LCD_RST") (class "Default")
      (node (ref "IC5") (pin "12") (pinfunction "PB0(ICP)_12") (pintype "bidirectional"))
      (node (ref "U4") (pin "8") (pinfunction "B5_8") (pintype "bidirectional"))
    )
    (net (code "36") (name "LCD_RST_3V") (class "Default")
      (node (ref "LCD") (pin "8") (pinfunction "8_8") (pintype "passive"))
      (node (ref "U4") (pin "5") (pinfunction "A5_5") (pintype "bidirectional"))
    )
    (net (code "37") (name "LCD_RS_3V") (class "Default")
      (node (ref "LCD") (pin "7") (pinfunction "7_7") (pintype "passive"))
      (node (ref "U4") (pin "4") (pinfunction "A4_4") (pintype "bidirectional"))
    )
    (net (code "38") (name "LCD_SCK_3V") (class "Default")
      (node (ref "LCD") (pin "5") (pinfunction "5_5") (pintype "passive"))
      (node (ref "U4") (pin "2") (pinfunction "A2_2") (pintype "bidirectional"))
    )
    (net (code "39") (name "MISO") (class "Default")
      (node (ref "IC5") (pin "16") (pinfunction "PB4(MISO)_16") (pintype "bidirectional"))
      (node (ref "SV1") (pin "1") (pinfunction "1_1") (pintype "passive"))
    )
    (net (code "40") (name "MOD_OUT") (class "Default")
      (node (ref "MR10") (pin "P$2") (pinfunction "2_P$2") (pintype "passive"))
      (node (ref "MR11") (pin "P$2") (pinfunction "2_P$2") (pintype "passive"))
      (node (ref "MR6") (pin "P$2") (pinfunction "2_P$2") (pintype "passive"))
      (node (ref "MR7") (pin "P$1") (pinfunction "1_P$1") (pintype "passive"))
      (node (ref "RJH1") (pin "P$2") (pinfunction "2_P$2") (pintype "passive"))
      (node (ref "U2") (pin "5") (pinfunction "+IN_5") (pintype "input"))
    )
    (net (code "41") (name "MOSI") (class "Default")
      (node (ref "IC5") (pin "15") (pinfunction "PB3(MOSI/OC2)_15") (pintype "bidirectional"))
      (node (ref "SV1") (pin "4") (pinfunction "4_4") (pintype "passive"))
      (node (ref "U4") (pin "12") (pinfunction "B1_12") (pintype "bidirectional"))
    )
    (net (code "42") (name "N$11") (class "Default")
      (node (ref "IC7") (pin "1") (pinfunction "G_1") (pintype "passive"))
      (node (ref "IC8") (pin "P$1") (pinfunction "G_P$1") (pintype "passive"))
      (node (ref "QFB1") (pin "1") (pinfunction "G_1") (pintype "passive"))
      (node (ref "R1") (pin "P$2") (pinfunction "2_P$2") (pintype "passive"))
      (node (ref "R2") (pin "P$1") (pinfunction "1_P$1") (pintype "passive"))
    )
    (net (code "43") (name "N$15") (class "Default")
      (node (ref "IC7") (pin "2") (pinfunction "S_2") (pintype "passive"))
      (node (ref "IC8") (pin "P$2") (pinfunction "S_P$2") (pintype "passive"))
      (node (ref "QFB1") (pin "2") (pinfunction "S_2") (pintype "passive"))
      (node (ref "R16") (pin "P$1") (pinfunction "1_P$1") (pintype "passive"))
      (node (ref "RS1") (pin "1") (pinfunction "1_1") (pintype "passive"))
      (node (ref "RS2") (pin "1") (pinfunction "1_1") (pintype "passive"))
      (node (ref "U3") (pin "2") (pinfunction "-IN_2") (pintype "input"))
    )
    (net (code "44") (name "Net-(BUFA-+IN)") (class "Default")
      (node (ref "BUF") (pin "3") (pinfunction "+IN_3") (pintype "input"))
      (node (ref "R13") (pin "P$6") (pinfunction "2_P$6") (pintype "passive"))
      (node (ref "R13") (pin "P$8") (pinfunction "2_P$8") (pintype "passive"))
    )
    (net (code "45") (name "Net-(BUFA--IN)") (class "Default")
      (node (ref "BUF") (pin "2") (pinfunction "-IN_2") (pintype "input"))
      (node (ref "R13") (pin "P$2") (pinfunction "2_P$2") (pintype "passive"))
      (node (ref "R13") (pin "P$4") (pinfunction "2_P$4") (pintype "passive"))
    )
    (net (code "46") (name "Net-(BUFA-OUT)") (class "Default")
      (node (ref "BUF") (pin "1") (pinfunction "OUT_1") (pintype "output"))
      (node (ref "MON1") (pin "P$1") (pinfunction "1_P$1") (pintype "passive"))
      (node (ref "R13") (pin "P$3") (pinfunction "1_P$3") (pintype "passive"))
    )
    (net (code "47") (name "Net-(BUFB-+IN)") (class "Default")
      (node (ref "BUF") (pin "5") (pinfunction "+IN_5") (pintype "input"))
      (node (ref "R16") (pin "P$2") (pinfunction "2_P$2") (pintype "passive"))
    )
    (net (code "48") (name "Net-(BUFB--IN)") (class "Default")
      (node (ref "BUF") (pin "6") (pinfunction "-IN_6") (pintype "input"))
      (node (ref "BUF") (pin "7") (pinfunction "OUT_7") (pintype "output"))
      (node (ref "R13") (pin "P$1") (pinfunction "1_P$1") (pintype "passive"))
    )
    (net (code "49") (name "Net-(BUFC-V+)") (class "Default")
      (node (ref "BUF") (pin "8") (pinfunction "V+_8") (pintype "power_in"))
      (node (ref "CL3") (pin "P$1") (pinfunction "1_P$1") (pintype "passive"))
      (node (ref "CR3") (pin "P$1") (pinfunction "1_P$1") (pintype "passive"))
      (node (ref "F3") (pin "P$1") (pinfunction "1_P$1") (pintype "passive"))
    )
    (net (code "50") (name "Net-(BUFC-V-)") (class "Default")
      (node (ref "BUF") (pin "4") (pinfunction "V-_4") (pintype "power_in"))
      (node (ref "CL4") (pin "P$1") (pinfunction "1_P$1") (pintype "passive"))
      (node (ref "CR4") (pin "P$1") (pinfunction "1_P$1") (pintype "passive"))
      (node (ref "F4") (pin "P$1") (pinfunction "1_P$1") (pintype "passive"))
    )
    (net (code "51") (name "Net-(C2-1)") (class "Default")
      (node (ref "C2") (pin "P$1") (pinfunction "1_P$1") (pintype "passive"))
      (node (ref "U1") (pin "14") (pinfunction "NR_14") (pintype "bidirectional"))
    )
    (net (code "52") (name "Net-(C3-2)") (class "Default")
      (node (ref "C3") (pin "P$2") (pinfunction "2_P$2") (pintype "passive"))
      (node (ref "R2") (pin "P$2") (pinfunction "2_P$2") (pintype "passive"))
    )
    (net (code "53") (name "Net-(C4-2)") (class "Default")
      (node (ref "C4") (pin "P$2") (pinfunction "2_P$2") (pintype "passive"))
      (node (ref "C7") (pin "P$2") (pinfunction "2_P$2") (pintype "passive"))
      (node (ref "R4") (pin "P$1") (pinfunction "1_P$1") (pintype "passive"))
      (node (ref "R5") (pin "P$2") (pinfunction "2_P$2") (pintype "passive"))
    )
    (net (code "54") (name "Net-(C5-2)") (class "Default")
      (node (ref "C5") (pin "P$2") (pinfunction "2_P$2") (pintype "passive"))
      (node (ref "C8") (pin "P$2") (pinfunction "2_P$2") (pintype "passive"))
      (node (ref "R14") (pin "P$2") (pinfunction "2_P$2") (pintype "passive"))
      (node (ref "R5") (pin "P$1") (pinfunction "1_P$1") (pintype "passive"))
    )
    (net (code "55") (name "Net-(C6-2)") (class "Default")
      (node (ref "C6") (pin "P$2") (pinfunction "2_P$2") (pintype "passive"))
      (node (ref "C9") (pin "P$2") (pinfunction "2_P$2") (pintype "passive"))
      (node (ref "R15") (pin "P$2") (pinfunction "2_P$2") (pintype "passive"))
      (node (ref "R50") (pin "P$1") (pinfunction "1_P$1") (pintype "passive"))
    )
    (net (code "56") (name "Net-(C11-1)") (class "Default")
      (node (ref "C11") (pin "P$1") (pinfunction "1_P$1") (pintype "passive"))
      (node (ref "C21") (pin "P$1") (pinfunction "1_P$1") (pintype "passive"))
      (node (ref "C22") (pin "P$1") (pinfunction "1_P$1") (pintype "passive"))
      (node (ref "C23") (pin "P$1") (pinfunction "1_P$1") (pintype "passive"))
      (node (ref "DAC1") (pin "3") (pinfunction "REF_3") (pintype "bidirectional"))
      (node (ref "DAC1") (pin "8") (pinfunction "VDD_8") (pintype "bidirectional"))
      (node (ref "F8") (pin "P$2") (pinfunction "2_P$2") (pintype "passive"))
    )
    (net (code "57") (name "Net-(C18-2)") (class "Default")
      (node (ref "C18") (pin "P$2") (pinfunction "2_P$2") (pintype "passive"))
      (node (ref "MR12") (pin "P$1") (pinfunction "1_P$1") (pintype "passive"))
      (node (ref "MR5") (pin "P$1") (pinfunction "1_P$1") (pintype "passive"))
      (node (ref "U2") (pin "3") (pinfunction "+IN_3") (pintype "input"))
    )
    (net (code "58") (name "Net-(C27-1)") (class "Default")
      (node (ref "C27") (pin "P$1") (pinfunction "1_P$1") (pintype "passive"))
      (node (ref "IC5") (pin "20") (pinfunction "AREF_20") (pintype "passive"))
    )
    (net (code "59") (name "Net-(D4-PadA)") (class "Default")
      (node (ref "D4") (pin "A") (pinfunction "A_A") (pintype "passive"))
      (node (ref "JP1") (pin "3") (pinfunction "3_3") (pintype "passive"))
    )
    (net (code "60") (name "Net-(FFWDA-+IN)") (class "Default")
      (node (ref "FFWD") (pin "3") (pinfunction "+IN_3") (pintype "input"))
      (node (ref "T1") (pin "P$2") (pinfunction "P$2_P$2") (pintype "bidirectional"))
    )
    (net (code "61") (name "Net-(FFWDB--IN)") (class "Default")
      (node (ref "FFWD") (pin "6") (pinfunction "-IN_6") (pintype "input"))
      (node (ref "R17") (pin "P$2") (pinfunction "2_P$2") (pintype "passive"))
      (node (ref "R18") (pin "P$1") (pinfunction "1_P$1") (pintype "passive"))
    )
    (net (code "62") (name "Net-(IC1-VI)") (class "Default")
      (node (ref "IC1") (pin "1") (pinfunction "VI_1") (pintype "input"))
      (node (ref "R6") (pin "P$2") (pinfunction "2_P$2") (pintype "passive"))
    )
    (net (code "63") (name "Net-(IC2-VI)") (class "Default")
      (node (ref "IC2") (pin "TAB") (pinfunction "VI_TAB") (pintype "input"))
      (node (ref "R3") (pin "P$2") (pinfunction "2_P$2") (pintype "passive"))
    )
    (net (code "64") (name "Net-(IC3A-+IN)") (class "Default")
      (node (ref "IC3") (pin "3") (pinfunction "+IN_3") (pintype "input"))
      (node (ref "R9") (pin "P$2") (pinfunction "2_P$2") (pintype "passive"))
      (node (ref "R9") (pin "P$4") (pinfunction "2_P$4") (pintype "passive"))
    )
    (net (code "65") (name "Net-(IC3A--IN)") (class "Default")
      (node (ref "IC3") (pin "2") (pinfunction "-IN_2") (pintype "input"))
      (node (ref "R9") (pin "P$6") (pinfunction "2_P$6") (pintype "passive"))
      (node (ref "R9") (pin "P$8") (pinfunction "2_P$8") (pintype "passive"))
    )
    (net (code "66") (name "Net-(IC3B-+IN)") (class "Default")
      (node (ref "IC3") (pin "5") (pinfunction "+IN_5") (pintype "input"))
      (node (ref "R10") (pin "P$1") (pinfunction "1_P$1") (pintype "passive"))
      (node (ref "R10") (pin "P$3") (pinfunction "1_P$3") (pintype "passive"))
    )
    (net (code "67") (name "Net-(IC3B--IN)") (class "Default")
      (node (ref "IC3") (pin "6") (pinfunction "-IN_6") (pintype "input"))
      (node (ref "R10") (pin "P$5") (pinfunction "1_P$5") (pintype "passive"))
      (node (ref "R10") (pin "P$7") (pinfunction "1_P$7") (pintype "passive"))
    )
    (net (code "68") (name "Net-(IC3C-+IN)") (class "Default")
      (node (ref "IC3") (pin "10") (pinfunction "+IN_10") (pintype "input"))
      (node (ref "R11") (pin "P$2") (pinfunction "2_P$2") (pintype "passive"))
      (node (ref "R11") (pin "P$4") (pinfunction "2_P$4") (pintype "passive"))
    )
    (net (code "69") (name "Net-(IC3C--IN)") (class "Default")
      (node (ref "IC3") (pin "9") (pinfunction "-IN_9") (pintype "input"))
      (node (ref "R11") (pin "P$6") (pinfunction "2_P$6") (pintype "passive"))
      (node (ref "R11") (pin "P$8") (pinfunction "2_P$8") (pintype "passive"))
    )
    (net (code "70") (name "Net-(IC3D--IN)") (class "Default")
      (node (ref "IC3") (pin "13") (pinfunction "-IN_13") (pintype "input"))
      (node (ref "IC3") (pin "14") (pinfunction "OUT_14") (pintype "output"))
    )
    (net (code "71") (name "Net-(IC5-ADC6)") (class "Default")
      (node (ref "IC5") (pin "19") (pinfunction "ADC6_19") (pintype "bidirectional"))
      (node (ref "R19") (pin "P$1") (pinfunction "1_P$1") (pintype "passive"))
      (node (ref "R21") (pin "P$2") (pinfunction "2_P$2") (pintype "passive"))
    )
    (net (code "72") (name "Net-(IC5-ADC7)") (class "Default")
      (node (ref "D1") (pin "C") (pinfunction "C_C") (pintype "passive"))
      (node (ref "IC5") (pin "22") (pinfunction "ADC7_22") (pintype "bidirectional"))
      (node (ref "R22") (pin "P$2") (pinfunction "2_P$2") (pintype "passive"))
      (node (ref "R23") (pin "P$1") (pinfunction "1_P$1") (pintype "passive"))
    )
    (net (code "73") (name "Net-(JP4-P$1)") (class "Default")
      (node (ref "JP4") (pin "1") (pinfunction "P$1_1") (pintype "bidirectional"))
      (node (ref "MOD_IN") (pin "1") (pinfunction "1_1") (pintype "passive"))
      (node (ref "MR7") (pin "P$2") (pinfunction "2_P$2") (pintype "passive"))
      (node (ref "MR8") (pin "P$1") (pinfunction "1_P$1") (pintype "passive"))
      (node (ref "R24") (pin "P$2") (pinfunction "2_P$2") (pintype "passive"))
    )
    (net (code "74") (name "Net-(JP4-P$2)") (class "Default")
      (node (ref "JP4") (pin "2") (pinfunction "P$2_2") (pintype "bidirectional"))
      (node (ref "R20") (pin "P$2") (pinfunction "2_P$2") (pintype "passive"))
    )
    (net (code "75") (name "Net-(L1-2)") (class "Default")
      (node (ref "CP3") (pin "+") (pinfunction "+_+") (pintype "passive"))
      (node (ref "L1") (pin "P$2") (pinfunction "2_P$2") (pintype "passive"))
      (node (ref "R6") (pin "P$1") (pinfunction "1_P$1") (pintype "passive"))
      (node (ref "R8") (pin "P$1") (pinfunction "1_P$1") (pintype "passive"))
    )
    (net (code "76") (name "Net-(L2-2)") (class "Default")
      (node (ref "CN3") (pin "-") (pinfunction "-_-") (pintype "passive"))
      (node (ref "L2") (pin "P$2") (pinfunction "2_P$2") (pintype "passive"))
      (node (ref "R3") (pin "P$1") (pinfunction "1_P$1") (pintype "passive"))
      (node (ref "R7") (pin "P$1") (pinfunction "1_P$1") (pintype "passive"))
    )
    (net (code "77") (name "Net-(MC1-1)") (class "Default")
      (node (ref "MC1") (pin "P$1") (pinfunction "1_P$1") (pintype "passive"))
      (node (ref "MR3") (pin "P$1") (pinfunction "1_P$1") (pintype "passive"))
      (node (ref "MR4") (pin "P$2") (pinfunction "2_P$2") (pintype "passive"))
      (node (ref "U2") (pin "2") (pinfunction "-IN_2") (pintype "input"))
    )
    (net (code "78") (name "Net-(MC1-2)") (class "Default")
      (node (ref "MC1") (pin "P$2") (pinfunction "2_P$2") (pintype "passive"))
      (node (ref "MR4") (pin "P$1") (pinfunction "1_P$1") (pintype "passive"))
      (node (ref "MR9") (pin "P$2") (pinfunction "2_P$2") (pintype "passive"))
      (node (ref "U2") (pin "1") (pinfunction "OUT_1") (pintype "output"))
    )
    (net (code "79") (name "Net-(MON-1)") (class "Default")
      (node (ref "MON") (pin "P$1") (pinfunction "1_P$1") (pintype "passive"))
      (node (ref "MON1") (pin "P$2") (pinfunction "2_P$2") (pintype "passive"))
    )
    (net (code "80") (name "Net-(MR1-2)") (class "Default")
      (node (ref "MR1") (pin "P$2") (pinfunction "2_P$2") (pintype "passive"))
      (node (ref "MR2") (pin "P$2") (pinfunction "2_P$2") (pintype "passive"))
      (node (ref "U2") (pin "6") (pinfunction "-IN_6") (pintype "input"))
    )
    (net (code "81") (name "Net-(MR8-2)") (class "Default")
      (node (ref "MR8") (pin "P$2") (pinfunction "2_P$2") (pintype "passive"))
      (node (ref "MR9") (pin "P$1") (pinfunction "1_P$1") (pintype "passive"))
    )
    (net (code "82") (name "Net-(MR11-1)") (class "Default")
      (node (ref "MR11") (pin "P$1") (pinfunction "1_P$1") (pintype "passive"))
      (node (ref "MR2") (pin "P$1") (pinfunction "1_P$1") (pintype "passive"))
      (node (ref "MR3") (pin "P$2") (pinfunction "2_P$2") (pintype "passive"))
      (node (ref "MR6") (pin "P$1") (pinfunction "1_P$1") (pintype "passive"))
      (node (ref "U2") (pin "7") (pinfunction "OUT_7") (pintype "output"))
    )
    (net (code "83") (name "Net-(R1-1)") (class "Default")
      (node (ref "R1") (pin "P$1") (pinfunction "1_P$1") (pintype "passive"))
      (node (ref "U3") (pin "1") (pinfunction "OUT_1") (pintype "output"))
    )
    (net (code "84") (name "Net-(R14-1)") (class "Default")
      (node (ref "R14") (pin "P$1") (pinfunction "1_P$1") (pintype "passive"))
      (node (ref "U3") (pin "3") (pinfunction "+IN_3") (pintype "input"))
    )
    (net (code "85") (name "Net-(R15-1)") (class "Default")
      (node (ref "R15") (pin "P$1") (pinfunction "1_P$1") (pintype "passive"))
      (node (ref "U3") (pin "5") (pinfunction "+IN_5") (pintype "input"))
    )
    (net (code "86") (name "Net-(R25-1)") (class "Default")
      (node (ref "R25") (pin "P$1") (pinfunction "1_P$1") (pintype "passive"))
      (node (ref "U4") (pin "14") (pinfunction "EN_14") (pintype "bidirectional"))
    )
    (net (code "87") (name "Net-(R36-1)") (class "Default")
      (node (ref "R36") (pin "P$1") (pinfunction "1_P$1") (pintype "passive"))
      (node (ref "R37") (pin "P$2") (pinfunction "2_P$2") (pintype "passive"))
      (node (ref "VREFIC") (pin "2") (pinfunction "2_2") (pintype "input"))
    )
    (net (code "88") (name "Net-(U1-0.1)") (class "Default")
      (node (ref "J3") (pin "P$16") (pinfunction "P$16_P$16") (pintype "bidirectional"))
      (node (ref "U1") (pin "12") (pinfunction "0.1_12") (pintype "bidirectional"))
    )
    (net (code "89") (name "Net-(U1-0.2)") (class "Default")
      (node (ref "J3") (pin "P$14") (pinfunction "P$14_P$14") (pintype "bidirectional"))
      (node (ref "U1") (pin "11") (pinfunction "0.2_11") (pintype "bidirectional"))
    )
    (net (code "90") (name "Net-(U1-0.4)") (class "Default")
      (node (ref "J3") (pin "P$12") (pinfunction "P$12_P$12") (pintype "bidirectional"))
      (node (ref "U1") (pin "10") (pinfunction "0.4_10") (pintype "bidirectional"))
    )
    (net (code "91") (name "Net-(U1-0.8)") (class "Default")
      (node (ref "J3") (pin "P$10") (pinfunction "P$10_P$10") (pintype "bidirectional"))
      (node (ref "U1") (pin "9") (pinfunction "0.8_9") (pintype "bidirectional"))
    )
    (net (code "92") (name "Net-(U1-1.6)") (class "Default")
      (node (ref "J3") (pin "P$8") (pinfunction "P$8_P$8") (pintype "bidirectional"))
      (node (ref "U1") (pin "8") (pinfunction "1.6_8") (pintype "bidirectional"))
    )
    (net (code "93") (name "Net-(U1-3.2)") (class "Default")
      (node (ref "J3") (pin "P$6") (pinfunction "P$6_P$6") (pintype "bidirectional"))
      (node (ref "U1") (pin "6") (pinfunction "3.2_6") (pintype "bidirectional"))
    )
    (net (code "94") (name "Net-(U1-6.4A)") (class "Default")
      (node (ref "J3") (pin "P$2") (pinfunction "P$2_P$2") (pintype "bidirectional"))
      (node (ref "U1") (pin "4") (pinfunction "6.4A_4") (pintype "bidirectional"))
    )
    (net (code "95") (name "Net-(U1-6.4B)") (class "Default")
      (node (ref "J3") (pin "P$4") (pinfunction "P$4_P$4") (pintype "bidirectional"))
      (node (ref "U1") (pin "5") (pinfunction "6.4B_5") (pintype "bidirectional"))
    )
    (net (code "96") (name "RESET") (class "Default")
      (node (ref "C28") (pin "P$2") (pinfunction "2_P$2") (pintype "passive"))
      (node (ref "IC5") (pin "29") (pinfunction "PC6(/RESET)_29") (pintype "bidirectional"))
      (node (ref "R100") (pin "P$1") (pinfunction "1_P$1") (pintype "passive"))
      (node (ref "SV1") (pin "5") (pinfunction "5_5") (pintype "passive"))
    )
    (net (code "97") (name "RXI") (class "Default")
      (node (ref "IC5") (pin "30") (pinfunction "PD0(RXD)_30") (pintype "bidirectional"))
      (node (ref "JP1") (pin "4") (pinfunction "4_4") (pintype "passive"))
    )
    (net (code "98") (name "SCK") (class "Default")
      (node (ref "IC5") (pin "17") (pinfunction "PB5(SCK)_17") (pintype "bidirectional"))
      (node (ref "SV1") (pin "3") (pinfunction "3_3") (pintype "passive"))
      (node (ref "U4") (pin "11") (pinfunction "B2_11") (pintype "bidirectional"))
    )
    (net (code "99") (name "SCL") (class "Default")
      (node (ref "IC5") (pin "28") (pinfunction "PC5(ADC5/SCL)_28") (pintype "bidirectional"))
      (node (ref "J1") (pin "C14") (pinfunction "C14_C14") (pintype "passive"))
    )
    (net (code "100") (name "SDA") (class "Default")
      (node (ref "IC5") (pin "27") (pinfunction "PC4(ADC4/SDA)_27") (pintype "bidirectional"))
      (node (ref "J1") (pin "A14") (pinfunction "A14_A14") (pintype "passive"))
    )
    (net (code "101") (name "SW") (class "Default")
      (node (ref "ENC") (pin "7") (pinfunction "7_7") (pintype "passive"))
      (node (ref "IC5") (pin "1") (pinfunction "PD3(INT1)_1") (pintype "bidirectional"))
    )
    (net (code "102") (name "TXO") (class "Default")
      (node (ref "IC5") (pin "31") (pinfunction "PD1(TXD)_31") (pintype "bidirectional"))
      (node (ref "JP1") (pin "5") (pinfunction "5_5") (pintype "passive"))
    )
    (net (code "103") (name "V+") (class "Default")
      (node (ref "C1") (pin "P$1") (pinfunction "+_P$1") (pintype "passive"))
      (node (ref "C29") (pin "P$1") (pinfunction "1_P$1") (pintype "passive"))
      (node (ref "CD1") (pin "P$1") (pinfunction "1_P$1") (pintype "passive"))
      (node (ref "CL12") (pin "P$1") (pinfunction "1_P$1") (pintype "passive"))
      (node (ref "CR12") (pin "P$1") (pinfunction "1_P$1") (pintype "passive"))
      (node (ref "F3") (pin "P$2") (pinfunction "2_P$2") (pintype "passive"))
      (node (ref "F9") (pin "P$1") (pinfunction "1_P$1") (pintype "passive"))
      (node (ref "IC1") (pin "3") (pinfunction "VO_3") (pintype "passive"))
      (node (ref "IC3") (pin "4") (pinfunction "V+_4") (pintype "power_in"))
      (node (ref "IC4") (pin "1") (pinfunction "IN_1") (pintype "bidirectional"))
      (node (ref "IC4") (pin "3") (pinfunction "EN_3") (pintype "bidirectional"))
      (node (ref "R19") (pin "P$2") (pinfunction "2_P$2") (pintype "passive"))
      (node (ref "R8") (pin "P$2") (pinfunction "2_P$2") (pintype "passive"))
      (node (ref "U1") (pin "15") (pinfunction "IN_15") (pintype "bidirectional"))
      (node (ref "U1") (pin "16") (pinfunction "IN_16") (pintype "bidirectional"))
      (node (ref "VREFIC") (pin "3") (pinfunction "3_3") (pintype "input"))
    )
    (net (code "104") (name "V-") (class "Default")
      (node (ref "C24") (pin "P$1") (pinfunction "1_P$1") (pintype "passive"))
      (node (ref "CD2") (pin "P$1") (pinfunction "1_P$1") (pintype "passive"))
      (node (ref "F4") (pin "P$2") (pinfunction "2_P$2") (pintype "passive"))
      (node (ref "F7") (pin "P$1") (pinfunction "1_P$1") (pintype "passive"))
      (node (ref "IC2") (pin "3") (pinfunction "VO_3") (pintype "passive"))
      (node (ref "IC3") (pin "11") (pinfunction "V-_11") (pintype "power_in"))
      (node (ref "R22") (pin "P$1") (pinfunction "1_P$1") (pintype "passive"))
      (node (ref "R37") (pin "P$1") (pinfunction "1_P$1") (pintype "passive"))
      (node (ref "R7") (pin "P$2") (pinfunction "2_P$2") (pintype "passive"))
      (node (ref "VREFIC") (pin "4") (pinfunction "4_4") (pintype "input"))
    )
    (net (code "105") (name "VCC") (class "Default")
      (node (ref "C19") (pin "P$1") (pinfunction "1_P$1") (pintype "passive"))
      (node (ref "D2") (pin "C") (pinfunction "C_C") (pintype "passive"))
      (node (ref "D4") (pin "C") (pinfunction "C_C") (pintype "passive"))
      (node (ref "ENC") (pin "1") (pinfunction "1_1") (pintype "passive"))
      (node (ref "IC4") (pin "5") (pinfunction "OUT_5") (pintype "bidirectional"))
      (node (ref "IC5") (pin "18") (pinfunction "AVCC_18") (pintype "power_in"))
      (node (ref "IC5") (pin "4") (pinfunction "VCC_4") (pintype "power_in"))
      (node (ref "IC5") (pin "6") (pinfunction "VCC_6") (pintype "power_in"))
      (node (ref "IC6") (pin "1") (pinfunction "IN_1") (pintype "bidirectional"))
      (node (ref "R100") (pin "P$2") (pinfunction "2_P$2") (pintype "passive"))
      (node (ref "R23") (pin "P$2") (pinfunction "2_P$2") (pintype "passive"))
      (node (ref "SV1") (pin "2") (pinfunction "2_2") (pintype "passive"))
    )
    (net (code "106") (name "VNEG_QUIET") (class "Default")
      (node (ref "C25") (pin "P$1") (pinfunction "1_P$1") (pintype "passive"))
      (node (ref "C26") (pin "P$1") (pinfunction "1_P$1") (pintype "passive"))
      (node (ref "C33") (pin "P$2") (pinfunction "2_P$2") (pintype "passive"))
      (node (ref "CL2") (pin "P$1") (pinfunction "1_P$1") (pintype "passive"))
      (node (ref "CL6") (pin "P$1") (pinfunction "1_P$1") (pintype "passive"))
      (node (ref "F7") (pin "P$2") (pinfunction "2_P$2") (pintype "passive"))
      (node (ref "FFWD") (pin "4") (pinfunction "V-_4") (pintype "power_in"))
      (node (ref "U2") (pin "4") (pinfunction "V-_4") (pintype "power_in"))
      (node (ref "U3") (pin "4") (pinfunction "V-_4") (pintype "power_in"))
    )
    (net (code "107") (name "VPOS_QUIET") (class "Default")
      (node (ref "C30") (pin "P$1") (pinfunction "1_P$1") (pintype "passive"))
      (node (ref "C31") (pin "P$1") (pinfunction "1_P$1") (pintype "passive"))
      (node (ref "C32") (pin "P$1") (pinfunction "1_P$1") (pintype "passive"))
      (node (ref "CL1") (pin "P$1") (pinfunction "1_P$1") (pintype "passive"))
      (node (ref "CL5") (pin "P$1") (pinfunction "1_P$1") (pintype "passive"))
      (node (ref "F9") (pin "P$2") (pinfunction "2_P$2") (pintype "passive"))
      (node (ref "FFWD") (pin "8") (pinfunction "V+_8") (pintype "power_in"))
      (node (ref "U2") (pin "8") (pinfunction "V+_8") (pintype "power_in"))
      (node (ref "U3") (pin "8") (pinfunction "V+_8") (pintype "power_in"))
    )
    (net (code "108") (name "VREF") (class "Default")
      (node (ref "R12") (pin "P$1") (pinfunction "1_P$1") (pintype "passive"))
      (node (ref "R36") (pin "P$2") (pinfunction "2_P$2") (pintype "passive"))
      (node (ref "R50") (pin "P$2") (pinfunction "2_P$2") (pintype "passive"))
    )
    (net (code "109") (name "VREG") (class "Default")
      (node (ref "C10") (pin "P$1") (pinfunction "1_P$1") (pintype "passive"))
      (node (ref "C12") (pin "P$1") (pinfunction "1_P$1") (pintype "passive"))
      (node (ref "C13") (pin "P$1") (pinfunction "1_P$1") (pintype "passive"))
      (node (ref "C14") (pin "P$1") (pinfunction "1_P$1") (pintype "passive"))
      (node (ref "C15") (pin "P$1") (pinfunction "1_P$1") (pintype "passive"))
      (node (ref "C16") (pin "P$1") (pinfunction "1_P$1") (pintype "passive"))
      (node (ref "C3") (pin "P$1") (pinfunction "1_P$1") (pintype "passive"))
      (node (ref "C4") (pin "P$1") (pinfunction "1_P$1") (pintype "passive"))
      (node (ref "C5") (pin "P$1") (pinfunction "1_P$1") (pintype "passive"))
      (node (ref "C6") (pin "P$1") (pinfunction "1_P$1") (pintype "passive"))
      (node (ref "C7") (pin "P$1") (pinfunction "1_P$1") (pintype "passive"))
      (node (ref "C8") (pin "P$1") (pinfunction "1_P$1") (pintype "passive"))
      (node (ref "C9") (pin "P$1") (pinfunction "1_P$1") (pintype "passive"))
      (node (ref "F8") (pin "P$1") (pinfunction "1_P$1") (pintype "passive"))
      (node (ref "R12") (pin "P$2") (pinfunction "2_P$2") (pintype "passive"))
      (node (ref "R13") (pin "P$5") (pinfunction "1_P$5") (pintype "passive"))
      (node (ref "RS1") (pin "2") (pinfunction "2_2") (pintype "passive"))
      (node (ref "RS2") (pin "2") (pinfunction "2_2") (pintype "passive"))
      (node (ref "U1") (pin "1") (pinfunction "OUT_1") (pintype "bidirectional"))
      (node (ref "U1") (pin "20") (pinfunction "OUT_20") (pintype "bidirectional"))
      (node (ref "U1") (pin "3") (pinfunction "SENSE_3") (pintype "bidirectional"))
      (node (ref "VREFIC") (pin "1") (pinfunction "1_1") (pintype "input"))
    )
    (net (code "110") (name "VREG_EN") (class "Default")
      (node (ref "IC5") (pin "2") (pinfunction "PD4(XCK/T0)_2") (pintype "bidirectional"))
      (node (ref "U1") (pin "13") (pinfunction "EN_13") (pintype "bidirectional"))
    )
    (net (code "111") (name "VSET") (class "Default")
      (node (ref "DAC1") (pin "1") (pinfunction "VOUT_1") (pintype "bidirectional"))
      (node (ref "R4") (pin "P$2") (pinfunction "2_P$2") (pintype "passive"))
    )
    (net (code "112") (name "VSS") (class "Default")
      (node (ref "C17") (pin "P$2") (pinfunction "2_P$2") (pintype "passive"))
      (node (ref "C19") (pin "P$2") (pinfunction "2_P$2") (pintype "passive"))
      (node (ref "C20") (pin "P$2") (pinfunction "2_P$2") (pintype "passive"))
      (node (ref "C27") (pin "P$2") (pinfunction "2_P$2") (pintype "passive"))
      (node (ref "D1") (pin "A") (pinfunction "A_A") (pintype "passive"))
      (node (ref "D2") (pin "A") (pinfunction "A_A") (pintype "passive"))
      (node (ref "D3") (pin "A") (pinfunction "A_A") (pintype "passive"))
      (node (ref "ENC") (pin "2") (pinfunction "2_2") (pintype "passive"))
      (node (ref "F1") (pin "P$1") (pinfunction "1_P$1") (pintype "passive"))
      (node (ref "IC4") (pin "2") (pinfunction "GND_2") (pintype "bidirectional"))
      (node (ref "IC5") (pin "21") (pinfunction "GND_21") (pintype "power_in"))
      (node (ref "IC5") (pin "3") (pinfunction "GND_3") (pintype "power_in"))
      (node (ref "IC5") (pin "5") (pinfunction "GND_5") (pintype "power_in"))
      (node (ref "IC6") (pin "2") (pinfunction "GND_2") (pintype "bidirectional"))
      (node (ref "JP1") (pin "1") (pinfunction "1_1") (pintype "passive"))
      (node (ref "JP1") (pin "2") (pinfunction "2_2") (pintype "passive"))
      (node (ref "LCD") (pin "2") (pinfunction "2_2") (pintype "passive"))
      (node (ref "LCD") (pin "4") (pinfunction "4_4") (pintype "passive"))
      (node (ref "R21") (pin "P$1") (pinfunction "1_P$1") (pintype "passive"))
      (node (ref "SV1") (pin "6") (pinfunction "6_6") (pintype "passive"))
      (node (ref "U$5") (pin "P$1") (pinfunction "GND_P$1") (pintype "bidirectional"))
      (node (ref "U$5") (pin "P$10") (pinfunction "GND_P$10") (pintype "bidirectional"))
      (node (ref "U$5") (pin "P$11") (pinfunction "GND_P$11") (pintype "bidirectional"))
      (node (ref "U$5") (pin "P$12") (pinfunction "GND_P$12") (pintype "bidirectional"))
      (node (ref "U$5") (pin "P$13") (pinfunction "GND_P$13") (pintype "bidirectional"))
      (node (ref "U$5") (pin "P$14") (pinfunction "GND_P$14") (pintype "bidirectional"))
      (node (ref "U$5") (pin "P$15") (pinfunction "GND_P$15") (pintype "bidirectional"))
      (node (ref "U$5") (pin "P$16") (pinfunction "GND_P$16") (pintype "bidirectional"))
      (node (ref "U$5") (pin "P$2") (pinfunction "GND_P$2") (pintype "bidirectional"))
      (node (ref "U$5") (pin "P$3") (pinfunction "GND_P$3") (pintype "bidirectional"))
      (node (ref "U$5") (pin "P$4") (pinfunction "GND_P$4") (pintype "bidirectional"))
      (node (ref "U$5") (pin "P$5") (pinfunction "GND_P$5") (pintype "bidirectional"))
      (node (ref "U$5") (pin "P$6") (pinfunction "GND_P$6") (pintype "bidirectional"))
      (node (ref "U$5") (pin "P$7") (pinfunction "GND_P$7") (pintype "bidirectional"))
      (node (ref "U$5") (pin "P$8") (pinfunction "GND_P$8") (pintype "bidirectional"))
      (node (ref "U$5") (pin "P$9") (pinfunction "GND_P$9") (pintype "bidirectional"))
      (node (ref "U4") (pin "15") (pinfunction "GND_15") (pintype "bidirectional"))
      (node (ref "U4") (pin "P$17") (pinfunction "GND_P$17") (pintype "bidirectional"))
    )
    (net (code "113") (name "unconnected-(ENC-Pad3)") (class "Default")
      (node (ref "ENC") (pin "3") (pinfunction "3_3") (pintype "passive"))
    )
    (net (code "114") (name "unconnected-(ENC-Pad5)") (class "Default")
      (node (ref "ENC") (pin "5") (pinfunction "5_5") (pintype "passive"))
    )
    (net (code "115") (name "unconnected-(IC4-BYP-Pad4)") (class "Default")
      (node (ref "IC4") (pin "4") (pinfunction "BYP_4") (pintype "bidirectional"))
    )
    (net (code "116") (name "unconnected-(IC5-PB6(XTAL1{slash}TOSC1)-Pad7)") (class "Default")
      (node (ref "IC5") (pin "7") (pinfunction "PB6(XTAL1/TOSC1)_7") (pintype "bidirectional"))
    )
    (net (code "117") (name "unconnected-(IC5-PB7(XTAL2{slash}TOSC2)-Pad8)") (class "Default")
      (node (ref "IC5") (pin "8") (pinfunction "PB7(XTAL2/TOSC2)_8") (pintype "bidirectional"))
    )
    (net (code "118") (name "unconnected-(IC5-PC3(ADC3)-Pad26)") (class "Default")
      (node (ref "IC5") (pin "26") (pinfunction "PC3(ADC3)_26") (pintype "bidirectional"))
    )
    (net (code "119") (name "unconnected-(IC6-BYP-Pad4)") (class "Default")
      (node (ref "IC6") (pin "4") (pinfunction "BYP_4") (pintype "bidirectional"))
    )
    (net (code "120") (name "unconnected-(J1-PadA2)") (class "Default")
      (node (ref "J1") (pin "A2") (pinfunction "A2_A2") (pintype "passive"))
    )
    (net (code "121") (name "unconnected-(J1-PadA5)") (class "Default")
      (node (ref "J1") (pin "A5") (pinfunction "A5_A5") (pintype "passive"))
    )
    (net (code "122") (name "unconnected-(J1-PadA8)") (class "Default")
      (node (ref "J1") (pin "A8") (pinfunction "A8_A8") (pintype "passive"))
    )
    (net (code "123") (name "unconnected-(J1-PadA9)") (class "Default")
      (node (ref "J1") (pin "A9") (pinfunction "A9_A9") (pintype "passive"))
    )
    (net (code "124") (name "unconnected-(J1-PadA10)") (class "Default")
      (node (ref "J1") (pin "A10") (pinfunction "A10_A10") (pintype "passive"))
    )
    (net (code "125") (name "unconnected-(J1-PadA11)") (class "Default")
      (node (ref "J1") (pin "A11") (pinfunction "A11_A11") (pintype "passive"))
    )
    (net (code "126") (name "unconnected-(J1-PadA12)") (class "Default")
      (node (ref "J1") (pin "A12") (pinfunction "A12_A12") (pintype "passive"))
    )
    (net (code "127") (name "unconnected-(J1-PadA13)") (class "Default")
      (node (ref "J1") (pin "A13") (pinfunction "A13_A13") (pintype "passive"))
    )
    (net (code "128") (name "unconnected-(J1-PadA15)") (class "Default")
      (node (ref "J1") (pin "A15") (pinfunction "A15_A15") (pintype "passive"))
    )
    (net (code "129") (name "unconnected-(J1-PadA16)") (class "Default")
      (node (ref "J1") (pin "A16") (pinfunction "A16_A16") (pintype "passive"))
    )
    (net (code "130") (name "unconnected-(J1-PadA17)") (class "Default")
      (node (ref "J1") (pin "A17") (pinfunction "A17_A17") (pintype "passive"))
    )
    (net (code "131") (name "unconnected-(J1-PadA18)") (class "Default")
      (node (ref "J1") (pin "A18") (pinfunction "A18_A18") (pintype "passive"))
    )
    (net (code "132") (name "unconnected-(J1-PadA19)") (class "Default")
      (node (ref "J1") (pin "A19") (pinfunction "A19_A19") (pintype "passive"))
    )
    (net (code "133") (name "unconnected-(J1-PadA20)") (class "Default")
      (node (ref "J1") (pin "A20") (pinfunction "A20_A20") (pintype "passive"))
    )
    (net (code "134") (name "unconnected-(J1-PadA21)") (class "Default")
      (node (ref "J1") (pin "A21") (pinfunction "A21_A21") (pintype "passive"))
    )
    (net (code "135") (name "unconnected-(J1-PadA22)") (class "Default")
      (node (ref "J1") (pin "A22") (pinfunction "A22_A22") (pintype "passive"))
    )
    (net (code "136") (name "unconnected-(J1-PadA23)") (class "Default")
      (node (ref "J1") (pin "A23") (pinfunction "A23_A23") (pintype "passive"))
    )
    (net (code "137") (name "unconnected-(J1-PadA24)") (class "Default")
      (node (ref "J1") (pin "A24") (pinfunction "A24_A24") (pintype "passive"))
    )
    (net (code "138") (name "unconnected-(J1-PadA25)") (class "Default")
      (node (ref "J1") (pin "A25") (pinfunction "A25_A25") (pintype "passive"))
    )
    (net (code "139") (name "unconnected-(J1-PadA26)") (class "Default")
      (node (ref "J1") (pin "A26") (pinfunction "A26_A26") (pintype "passive"))
    )
    (net (code "140") (name "unconnected-(J1-PadA27)") (class "Default")
      (node (ref "J1") (pin "A27") (pinfunction "A27_A27") (pintype "passive"))
    )
    (net (code "141") (name "unconnected-(J1-PadA28)") (class "Default")
      (node (ref "J1") (pin "A28") (pinfunction "A28_A28") (pintype "passive"))
    )
    (net (code "142") (name "unconnected-(J1-PadA29)") (class "Default")
      (node (ref "J1") (pin "A29") (pinfunction "A29_A29") (pintype "passive"))
    )
    (net (code "143") (name "unconnected-(J1-PadA32)") (class "Default")
      (node (ref "J1") (pin "A32") (pinfunction "A32_A32") (pintype "passive"))
    )
    (net (code "144") (name "unconnected-(J1-PadC2)") (class "Default")
      (node (ref "J1") (pin "C2") (pinfunction "C2_C2") (pintype "passive"))
    )
    (net (code "145") (name "unconnected-(J1-PadC5)") (class "Default")
      (node (ref "J1") (pin "C5") (pinfunction "C5_C5") (pintype "passive"))
    )
    (net (code "146") (name "unconnected-(J1-PadC8)") (class "Default")
      (node (ref "J1") (pin "C8") (pinfunction "C8_C8") (pintype "passive"))
    )
    (net (code "147") (name "unconnected-(J1-PadC9)") (class "Default")
      (node (ref "J1") (pin "C9") (pinfunction "C9_C9") (pintype "passive"))
    )
    (net (code "148") (name "unconnected-(J1-PadC10)") (class "Default")
      (node (ref "J1") (pin "C10") (pinfunction "C10_C10") (pintype "passive"))
    )
    (net (code "149") (name "unconnected-(J1-PadC11)") (class "Default")
      (node (ref "J1") (pin "C11") (pinfunction "C11_C11") (pintype "passive"))
    )
    (net (code "150") (name "unconnected-(J1-PadC12)") (class "Default")
      (node (ref "J1") (pin "C12") (pinfunction "C12_C12") (pintype "passive"))
    )
    (net (code "151") (name "unconnected-(J1-PadC13)") (class "Default")
      (node (ref "J1") (pin "C13") (pinfunction "C13_C13") (pintype "passive"))
    )
    (net (code "152") (name "unconnected-(J1-PadC15)") (class "Default")
      (node (ref "J1") (pin "C15") (pinfunction "C15_C15") (pintype "passive"))
    )
    (net (code "153") (name "unconnected-(J1-PadC16)") (class "Default")
      (node (ref "J1") (pin "C16") (pinfunction "C16_C16") (pintype "passive"))
    )
    (net (code "154") (name "unconnected-(J1-PadC17)") (class "Default")
      (node (ref "J1") (pin "C17") (pinfunction "C17_C17") (pintype "passive"))
    )
    (net (code "155") (name "unconnected-(J1-PadC18)") (class "Default")
      (node (ref "J1") (pin "C18") (pinfunction "C18_C18") (pintype "passive"))
    )
    (net (code "156") (name "unconnected-(J1-PadC19)") (class "Default")
      (node (ref "J1") (pin "C19") (pinfunction "C19_C19") (pintype "passive"))
    )
    (net (code "157") (name "unconnected-(J1-PadC20)") (class "Default")
      (node (ref "J1") (pin "C20") (pinfunction "C20_C20") (pintype "passive"))
    )
    (net (code "158") (name "unconnected-(J1-PadC21)") (class "Default")
      (node (ref "J1") (pin "C21") (pinfunction "C21_C21") (pintype "passive"))
    )
    (net (code "159") (name "unconnected-(J1-PadC22)") (class "Default")
      (node (ref "J1") (pin "C22") (pinfunction "C22_C22") (pintype "passive"))
    )
    (net (code "160") (name "unconnected-(J1-PadC23)") (class "Default")
      (node (ref "J1") (pin "C23") (pinfunction "C23_C23") (pintype "passive"))
    )
    (net (code "161") (name "unconnected-(J1-PadC24)") (class "Default")
      (node (ref "J1") (pin "C24") (pinfunction "C24_C24") (pintype "passive"))
    )
    (net (code "162") (name "unconnected-(J1-PadC25)") (class "Default")
      (node (ref "J1") (pin "C25") (pinfunction "C25_C25") (pintype "passive"))
    )
    (net (code "163") (name "unconnected-(J1-PadC26)") (class "Default")
      (node (ref "J1") (pin "C26") (pinfunction "C26_C26") (pintype "passive"))
    )
    (net (code "164") (name "unconnected-(J1-PadC27)") (class "Default")
      (node (ref "J1") (pin "C27") (pinfunction "C27_C27") (pintype "passive"))
    )
    (net (code "165") (name "unconnected-(J1-PadC28)") (class "Default")
      (node (ref "J1") (pin "C28") (pinfunction "C28_C28") (pintype "passive"))
    )
    (net (code "166") (name "unconnected-(J1-PadC29)") (class "Default")
      (node (ref "J1") (pin "C29") (pinfunction "C29_C29") (pintype "passive"))
    )
    (net (code "167") (name "unconnected-(J1-PadC32)") (class "Default")
      (node (ref "J1") (pin "C32") (pinfunction "C32_C32") (pintype "passive"))
    )
    (net (code "168") (name "unconnected-(U4-A6-Pad6)") (class "Default")
      (node (ref "U4") (pin "6") (pinfunction "A6_6") (pintype "bidirectional"))
    )
    (net (code "169") (name "unconnected-(U4-B6-Pad7)") (class "Default")
      (node (ref "U4") (pin "7") (pinfunction "B6_7") (pintype "bidirectional"))
    )
  )
)
